# tarjeta-v8.net
KiCad netlist of a schematic drawn in EAGLE
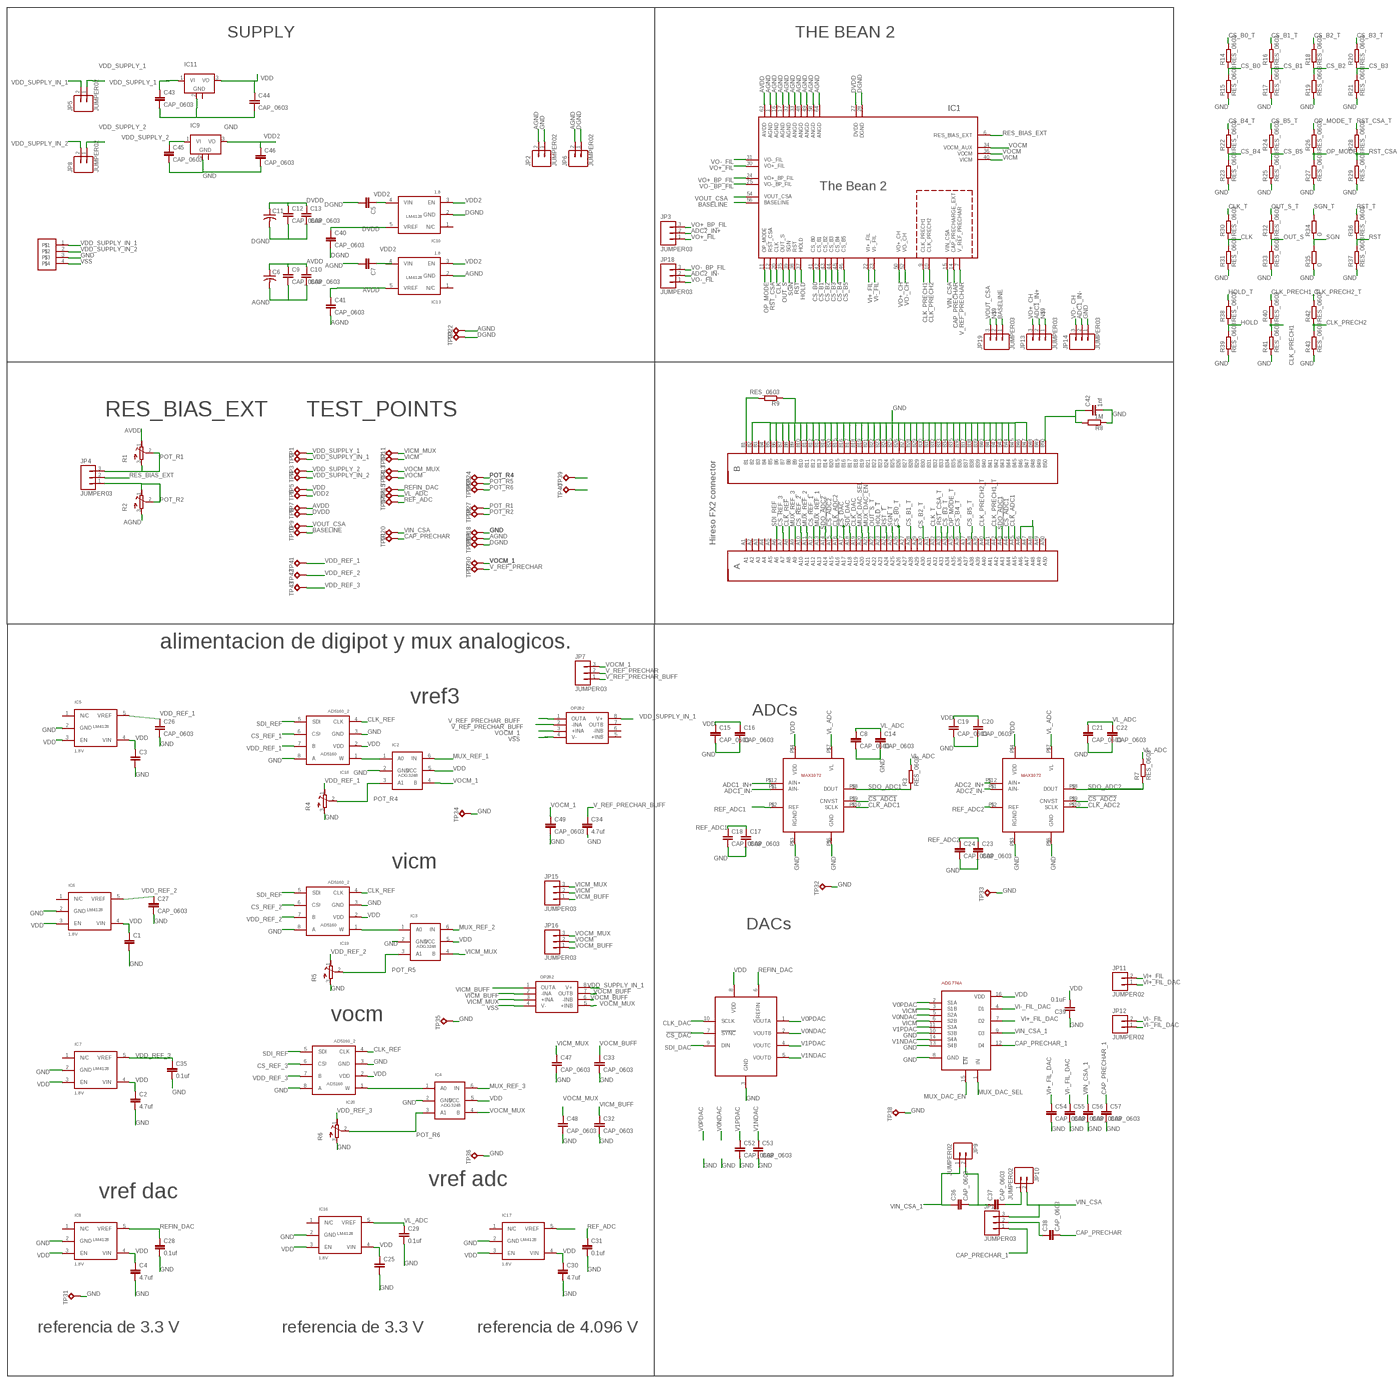
[diagram p0: schematic, sheet 1, overview]
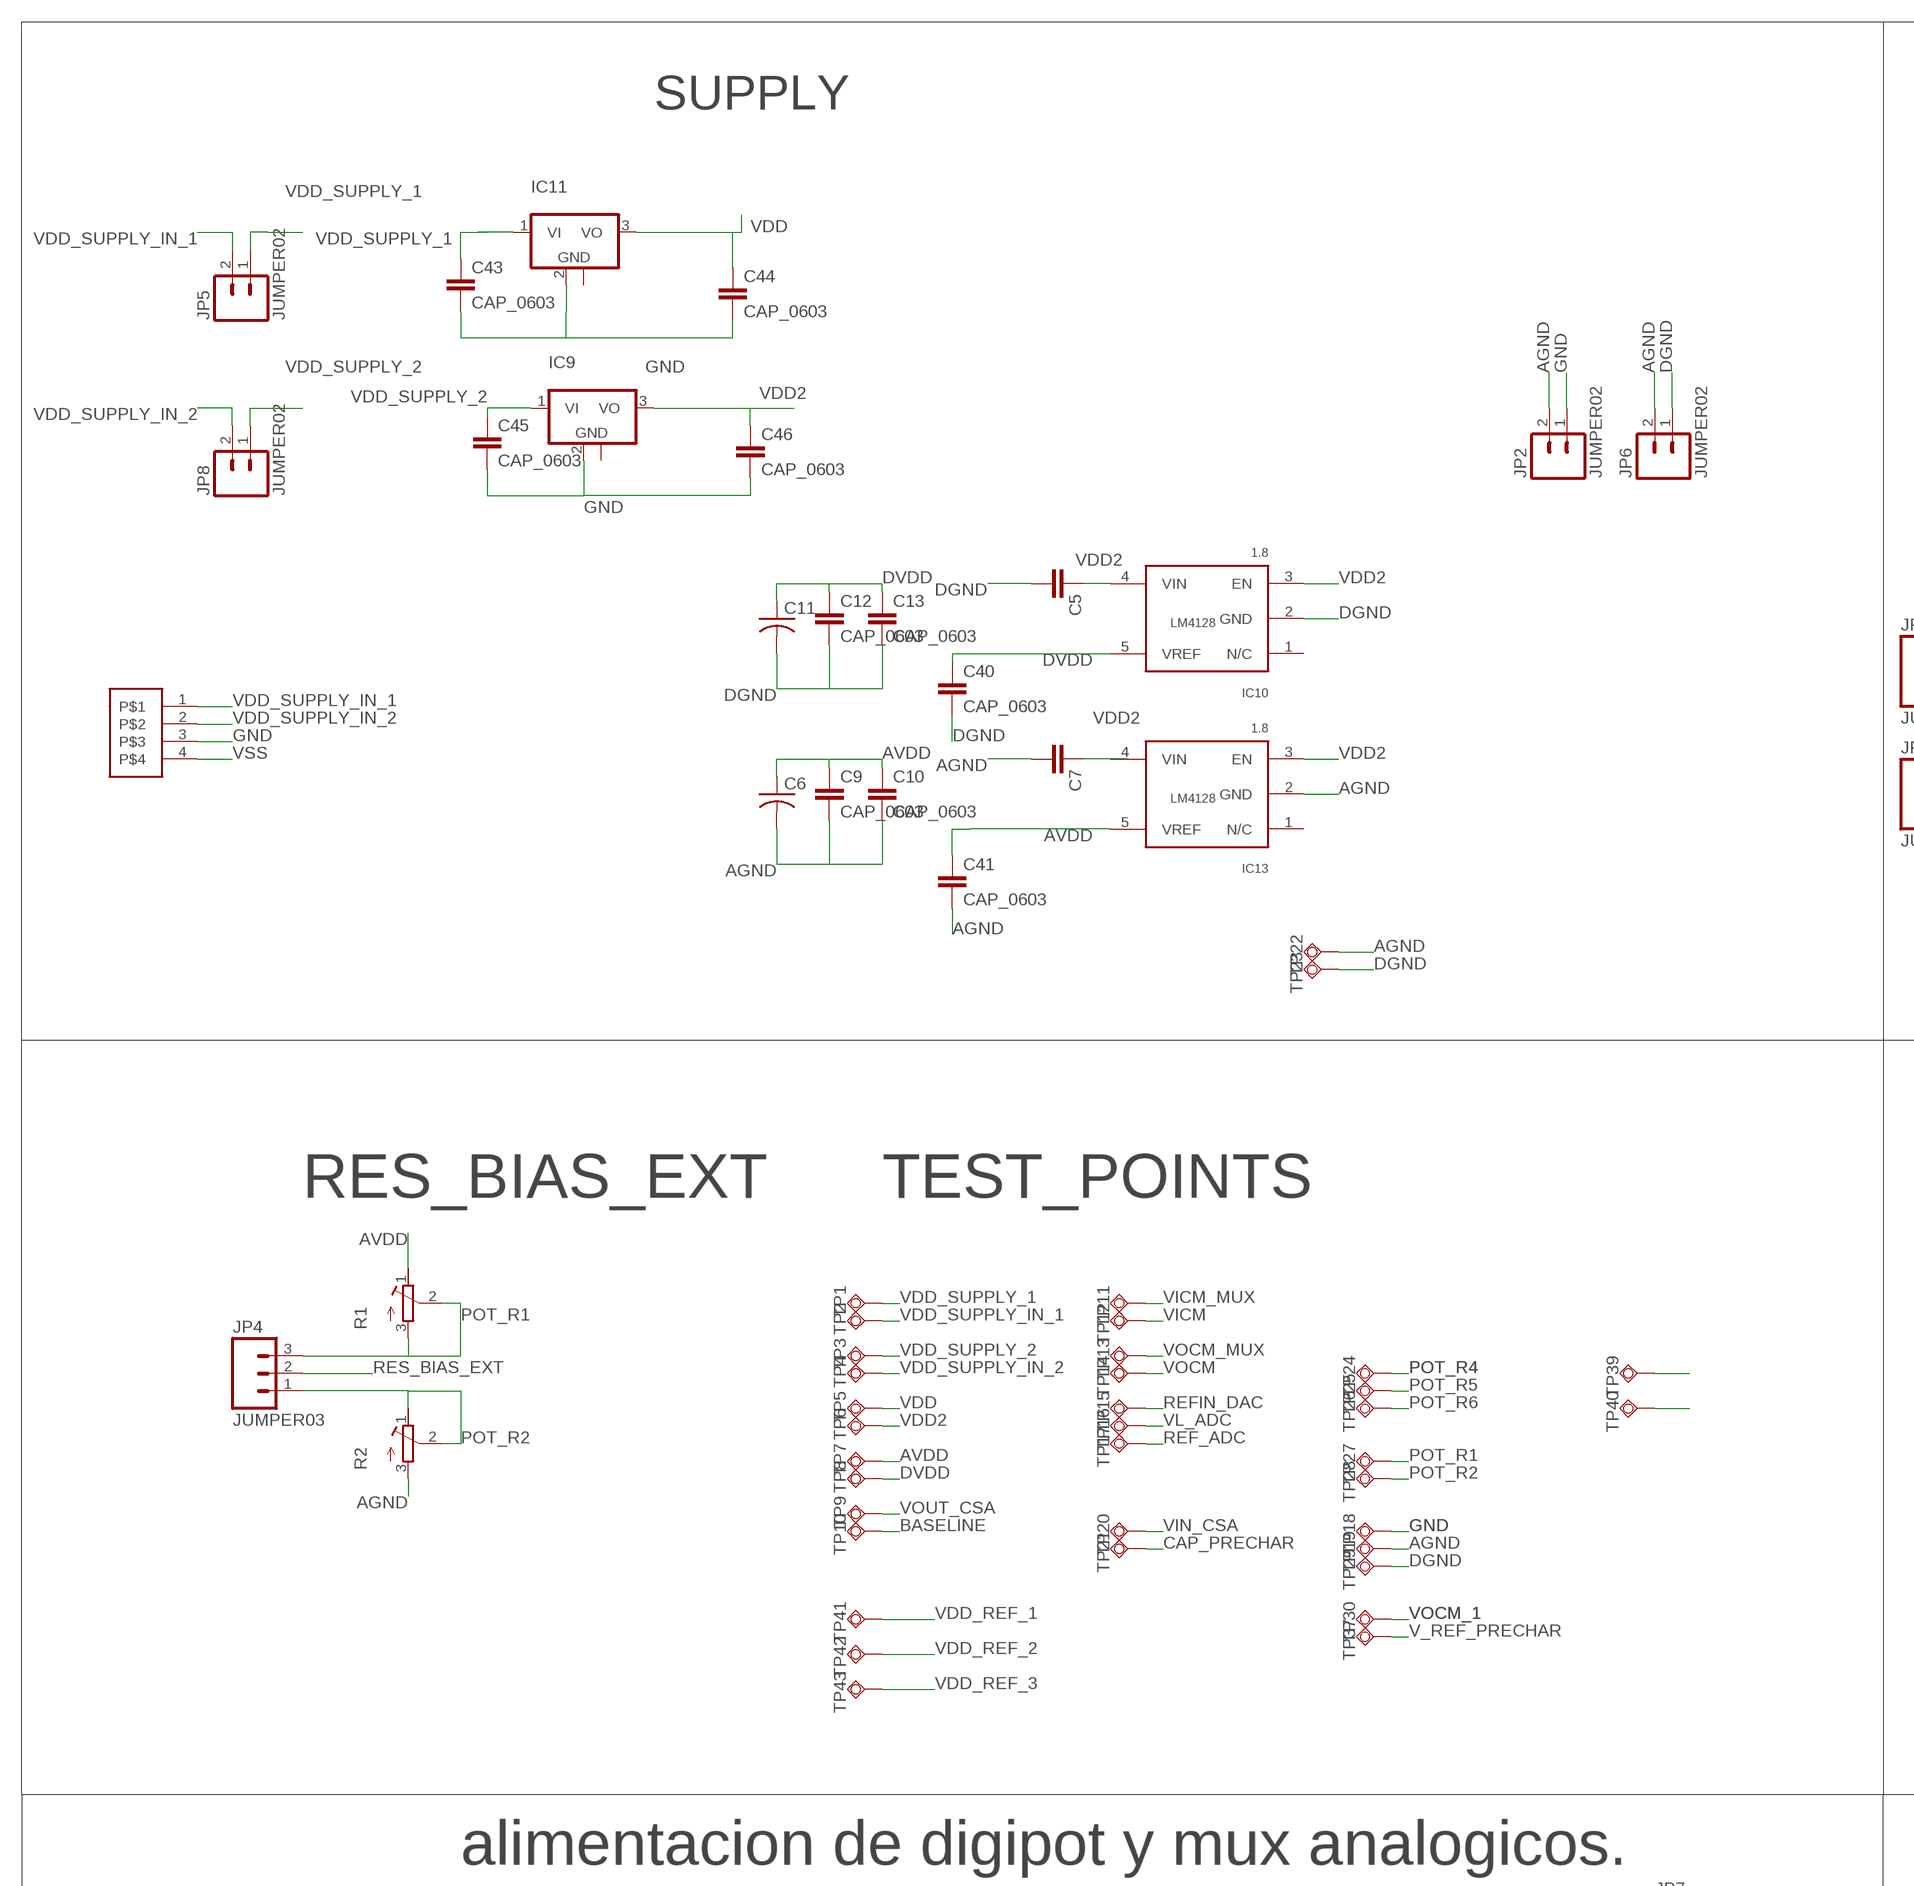
[diagram p1: schematic, sheet 1, part 1 of 4]
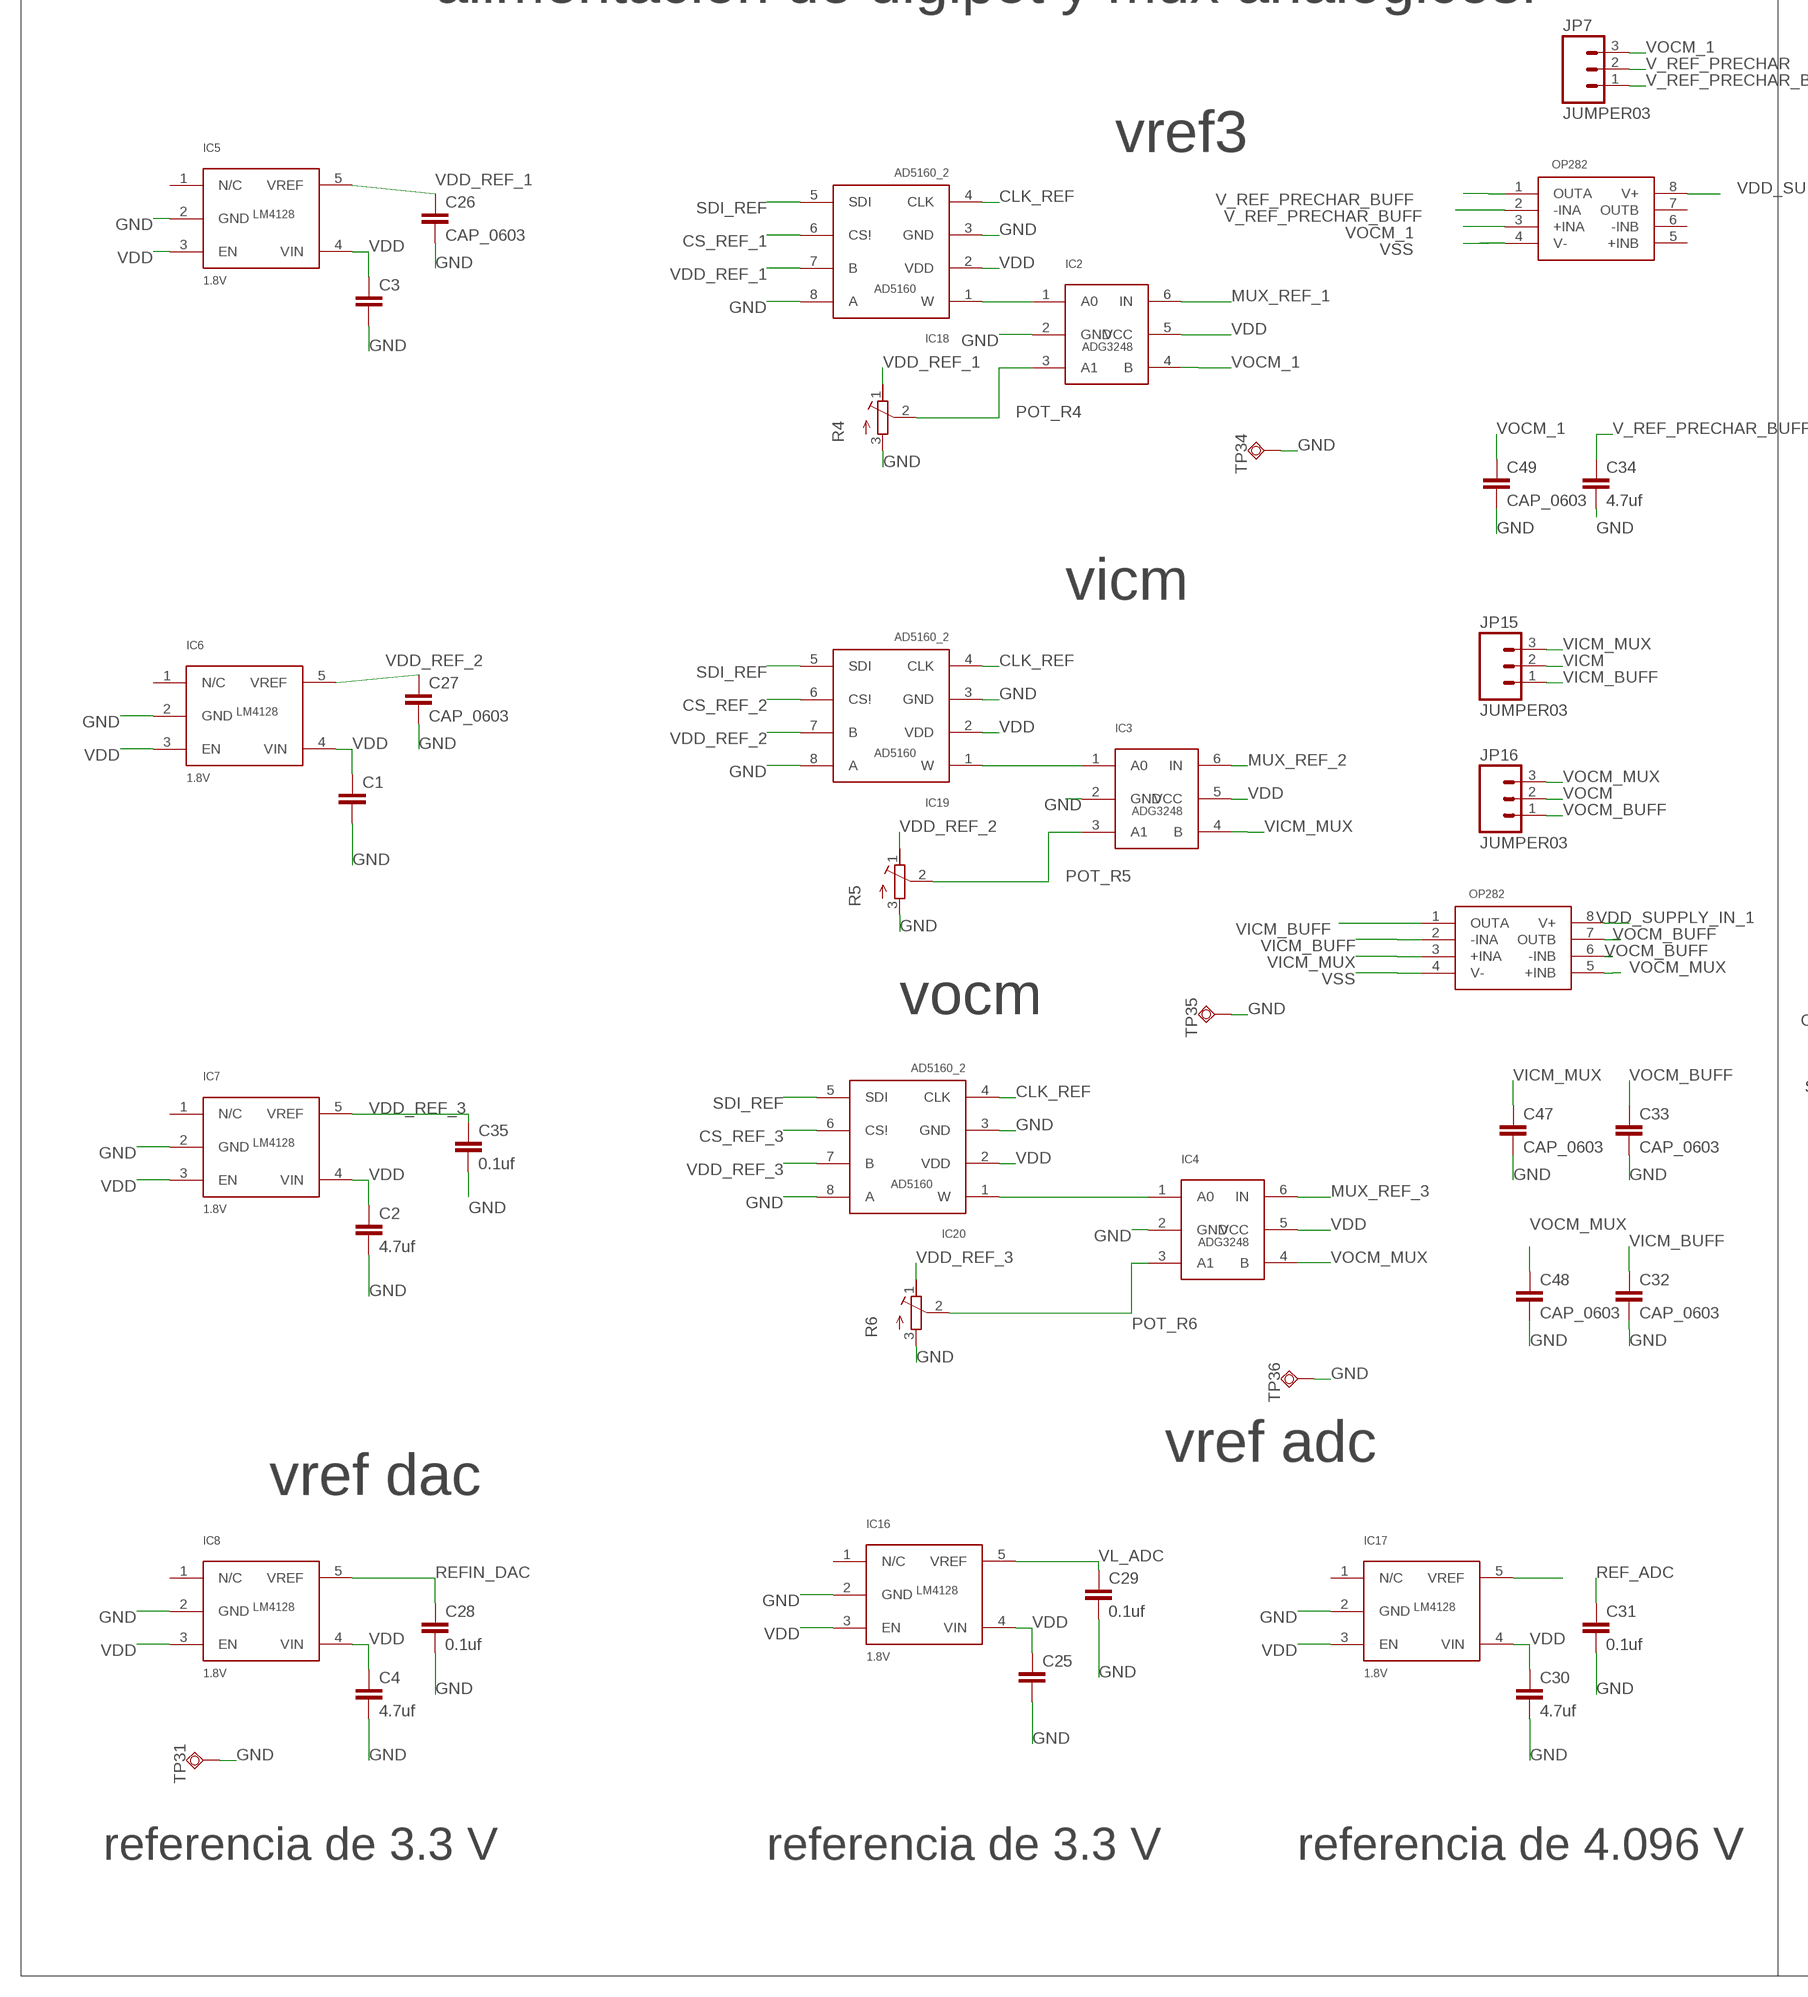
[diagram p2: schematic, sheet 1, part 2 of 4]
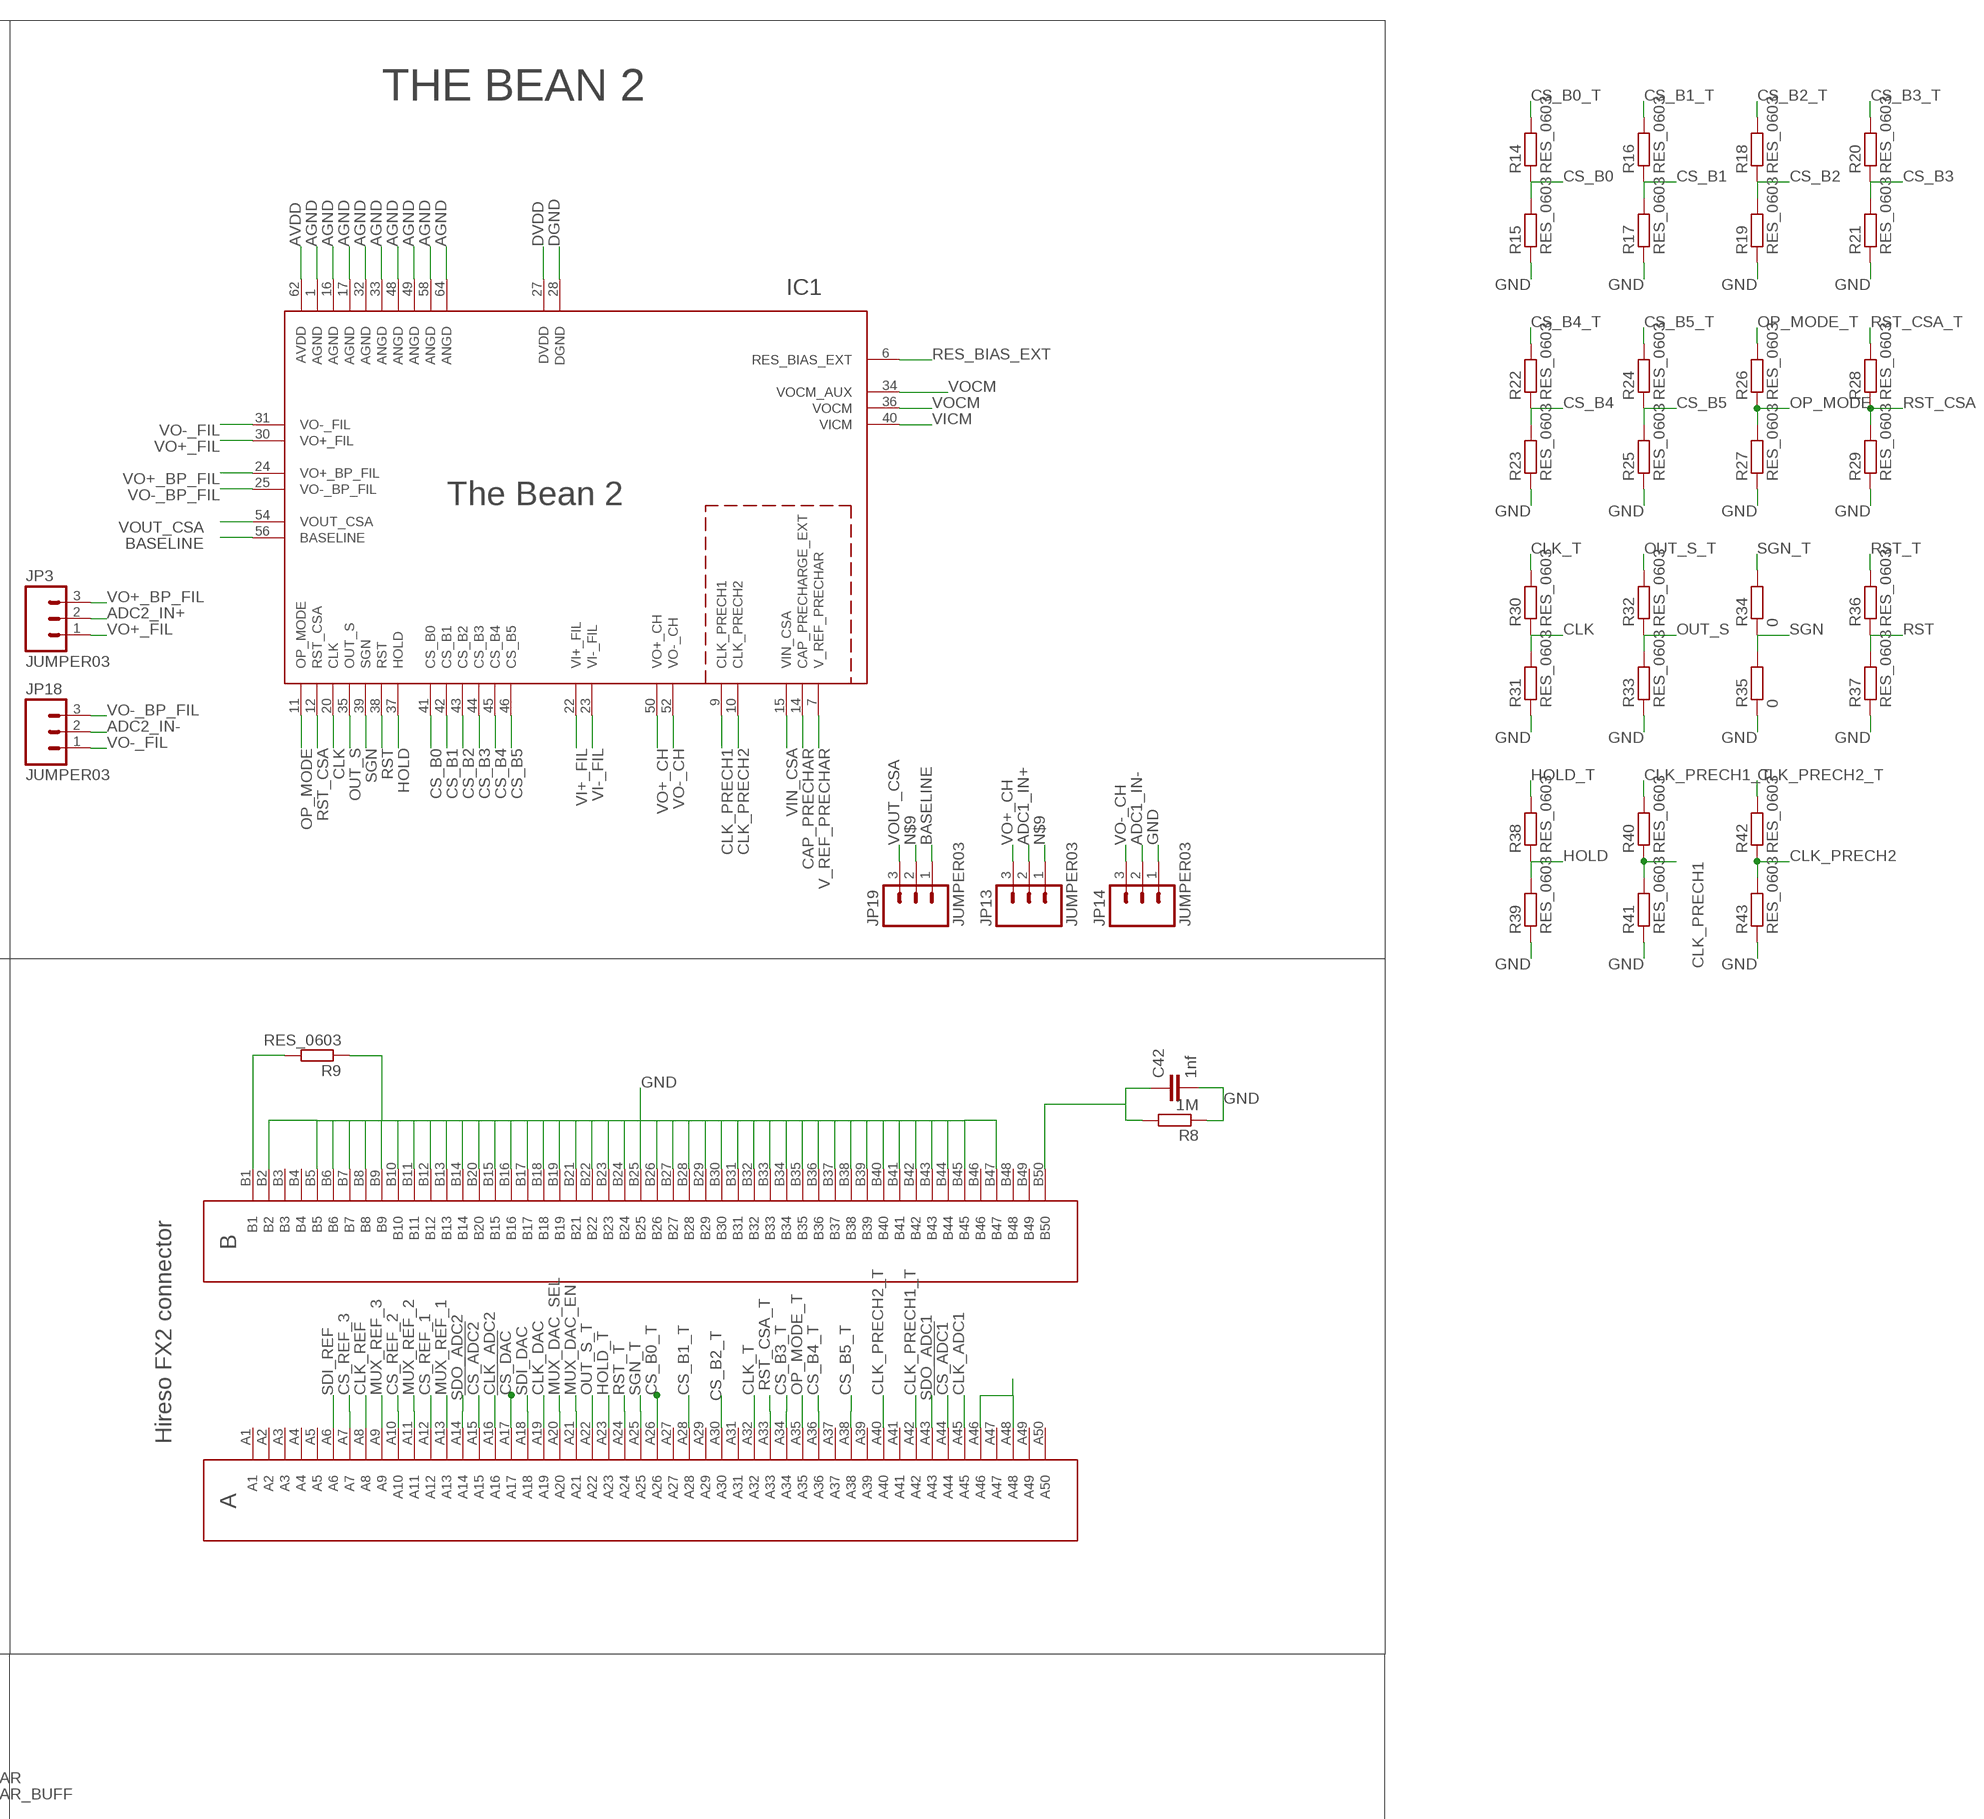
[diagram p3: schematic, sheet 1, part 3 of 4]
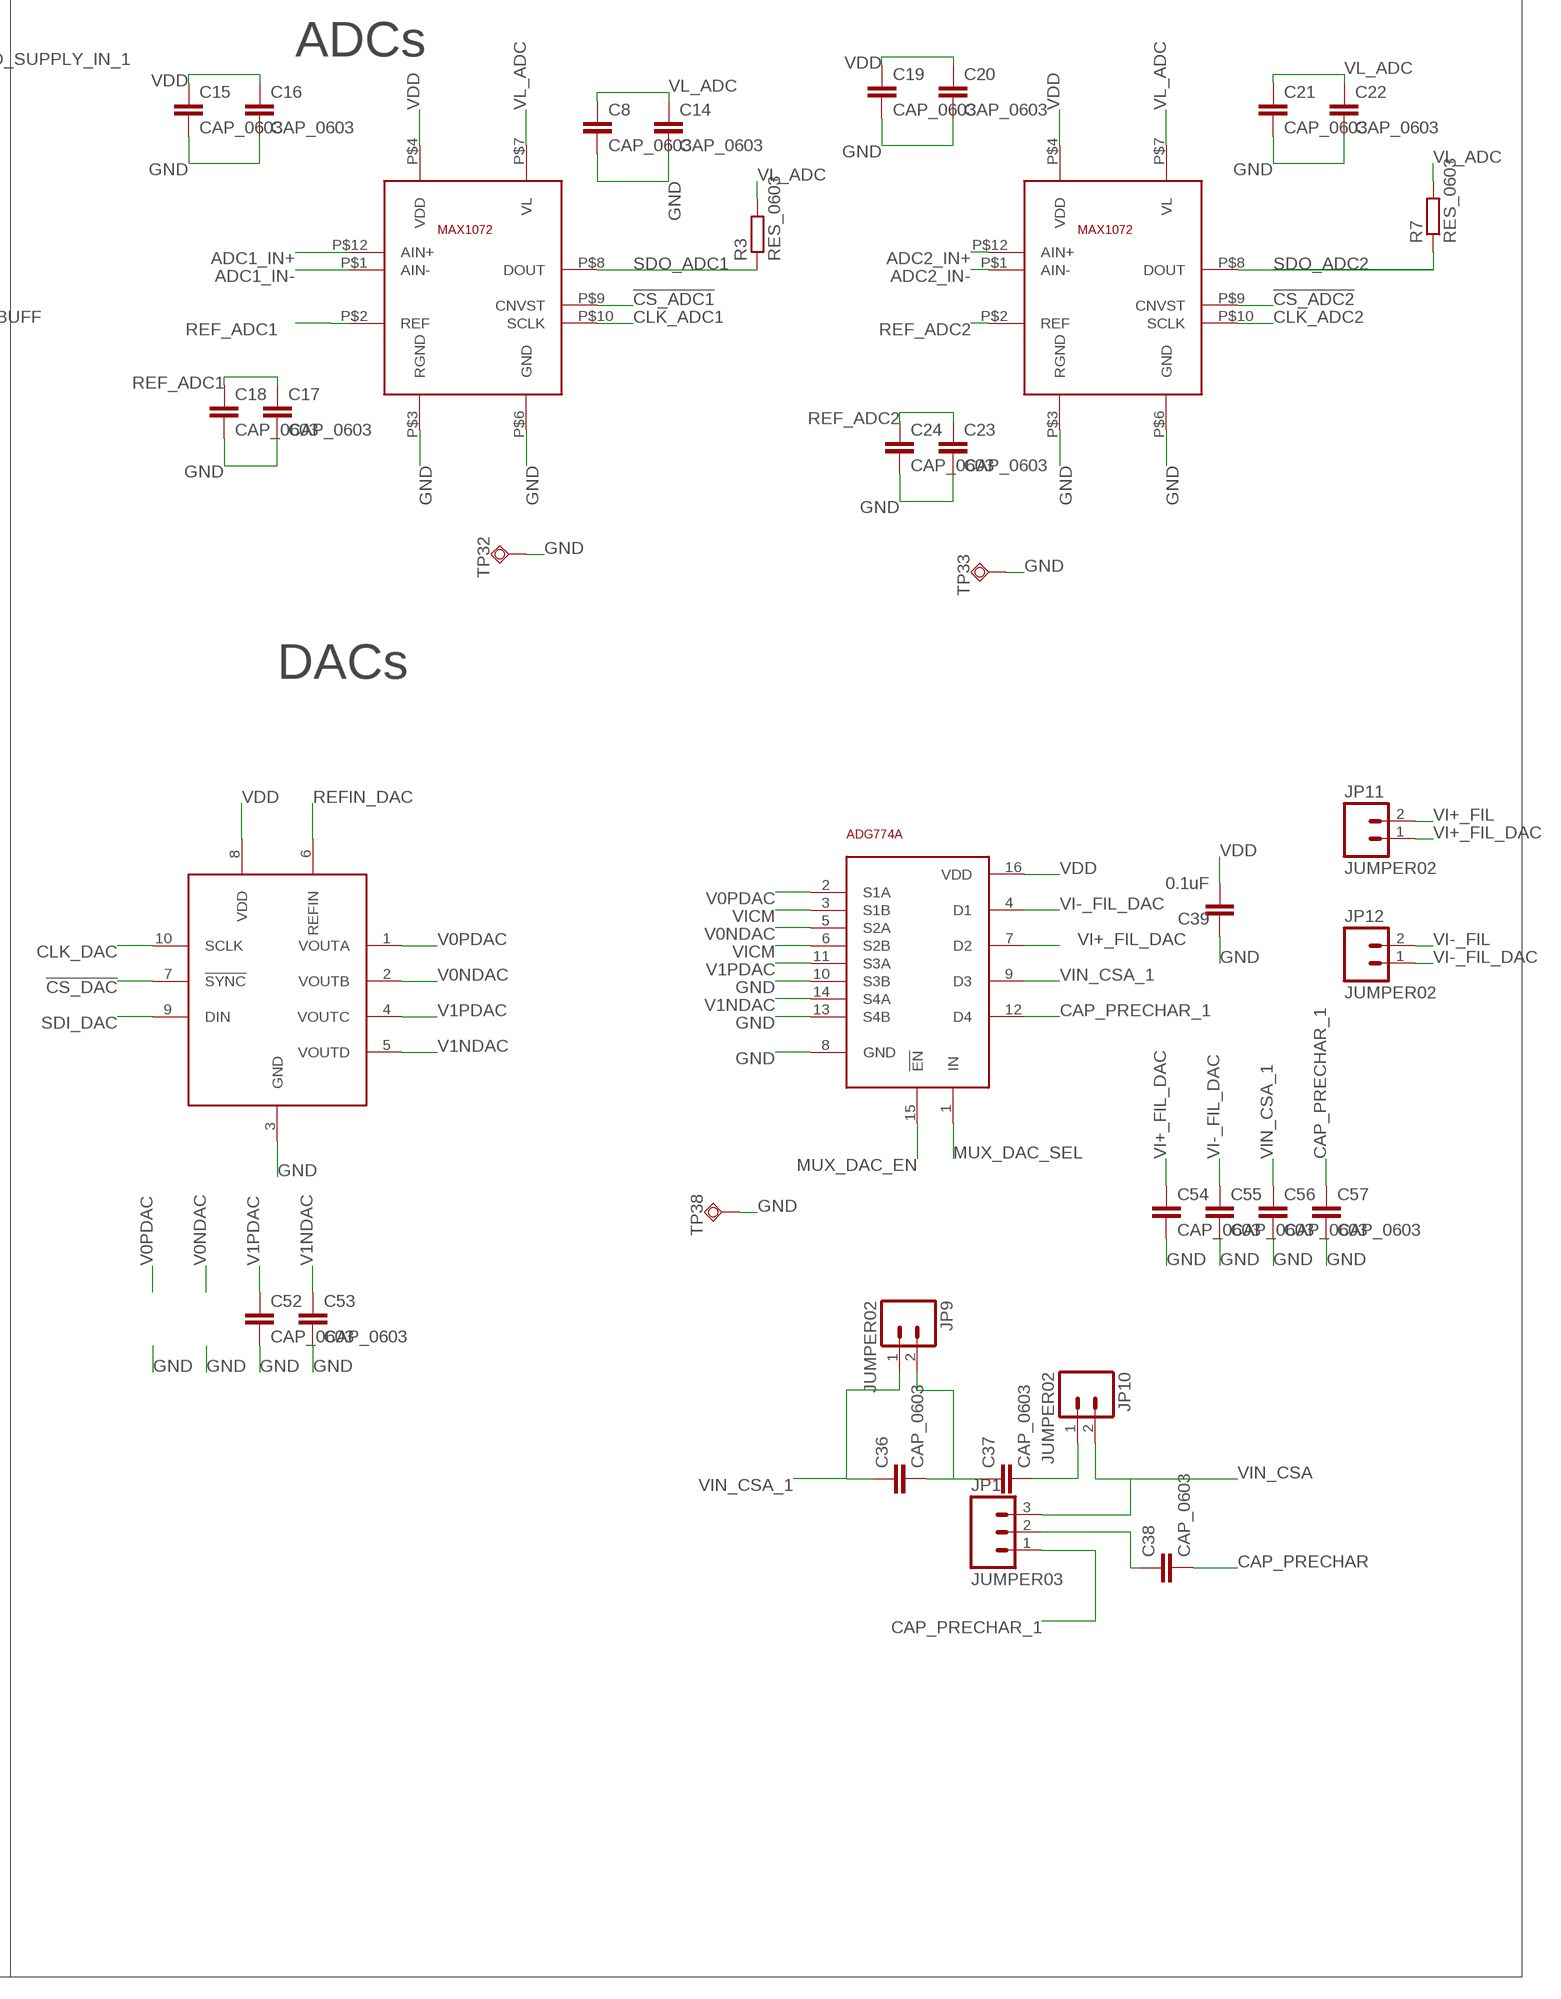
[diagram p4: schematic, sheet 1, part 4 of 4]

(export (version "E")
  (design (tool "Eeschema 10.0.6"))
  (components
    (comp (ref "C1")
      (value "CAP_0402")
      (footprint "eagle-import:C0402")
      (libsource (lib "eagle-import") (part "CAP_0402"))
    )
    (comp (ref "C2")
      (value "4.7uf")
      (footprint "eagle-import:C0402")
      (libsource (lib "eagle-import") (part "CAP_0402"))
    )
    (comp (ref "C3")
      (value "CAP_0402")
      (footprint "eagle-import:C0402")
      (libsource (lib "eagle-import") (part "CAP_0402"))
    )
    (comp (ref "C4")
      (value "4.7uf")
      (footprint "eagle-import:C0402")
      (libsource (lib "eagle-import") (part "CAP_0402"))
    )
    (comp (ref "C5")
      (value "CAP_0402")
      (footprint "eagle-import:C0402")
      (libsource (lib "eagle-import") (part "CAP_0402"))
    )
    (comp (ref "C6")
      (value "CAP_0805")
      (footprint "eagle-import:C0805")
      (libsource (lib "eagle-import") (part "CAP_0805"))
    )
    (comp (ref "C7")
      (value "CAP_0402")
      (footprint "eagle-import:C0402")
      (libsource (lib "eagle-import") (part "CAP_0402"))
    )
    (comp (ref "C8")
      (value "CAP_0603")
      (footprint "eagle-import:C0603")
      (libsource (lib "eagle-import") (part "CAP_0603"))
    )
    (comp (ref "C9")
      (value "CAP_0603")
      (footprint "eagle-import:C0603")
      (libsource (lib "eagle-import") (part "CAP_0603"))
    )
    (comp (ref "C10")
      (value "CAP_0603")
      (footprint "eagle-import:C0603")
      (libsource (lib "eagle-import") (part "CAP_0603"))
    )
    (comp (ref "C11")
      (value "CAP_0805")
      (footprint "eagle-import:C0805")
      (libsource (lib "eagle-import") (part "CAP_0805"))
    )
    (comp (ref "C12")
      (value "CAP_0603")
      (footprint "eagle-import:C0603")
      (libsource (lib "eagle-import") (part "CAP_0603"))
    )
    (comp (ref "C13")
      (value "CAP_0603")
      (footprint "eagle-import:C0603")
      (libsource (lib "eagle-import") (part "CAP_0603"))
    )
    (comp (ref "C14")
      (value "CAP_0603")
      (footprint "eagle-import:C0603")
      (libsource (lib "eagle-import") (part "CAP_0603"))
    )
    (comp (ref "C15")
      (value "CAP_0603")
      (footprint "eagle-import:C0603")
      (libsource (lib "eagle-import") (part "CAP_0603"))
    )
    (comp (ref "C16")
      (value "CAP_0603")
      (footprint "eagle-import:C0603")
      (libsource (lib "eagle-import") (part "CAP_0603"))
    )
    (comp (ref "C17")
      (value "CAP_0603")
      (footprint "eagle-import:C0603")
      (libsource (lib "eagle-import") (part "CAP_0603"))
    )
    (comp (ref "C18")
      (value "CAP_0603")
      (footprint "eagle-import:C0603")
      (libsource (lib "eagle-import") (part "CAP_0603"))
    )
    (comp (ref "C19")
      (value "CAP_0603")
      (footprint "eagle-import:C0603")
      (libsource (lib "eagle-import") (part "CAP_0603"))
    )
    (comp (ref "C20")
      (value "CAP_0603")
      (footprint "eagle-import:C0603")
      (libsource (lib "eagle-import") (part "CAP_0603"))
    )
    (comp (ref "C21")
      (value "CAP_0603")
      (footprint "eagle-import:C0603")
      (libsource (lib "eagle-import") (part "CAP_0603"))
    )
    (comp (ref "C22")
      (value "CAP_0603")
      (footprint "eagle-import:C0603")
      (libsource (lib "eagle-import") (part "CAP_0603"))
    )
    (comp (ref "C23")
      (value "CAP_0603")
      (footprint "eagle-import:C0603")
      (libsource (lib "eagle-import") (part "CAP_0603"))
    )
    (comp (ref "C24")
      (value "CAP_0603")
      (footprint "eagle-import:C0603")
      (libsource (lib "eagle-import") (part "CAP_0603"))
    )
    (comp (ref "C25")
      (value "CAP_0402")
      (footprint "eagle-import:C0402")
      (libsource (lib "eagle-import") (part "CAP_0402"))
    )
    (comp (ref "C26")
      (value "CAP_0603")
      (footprint "eagle-import:C0603")
      (libsource (lib "eagle-import") (part "CAP_0603"))
    )
    (comp (ref "C27")
      (value "CAP_0603")
      (footprint "eagle-import:C0603")
      (libsource (lib "eagle-import") (part "CAP_0603"))
    )
    (comp (ref "C28")
      (value "0.1uf")
      (footprint "eagle-import:C0603")
      (libsource (lib "eagle-import") (part "CAP_0603"))
    )
    (comp (ref "C29")
      (value "0.1uf")
      (footprint "eagle-import:C0603")
      (libsource (lib "eagle-import") (part "CAP_0603"))
    )
    (comp (ref "C30")
      (value "4.7uf")
      (footprint "eagle-import:C0402")
      (libsource (lib "eagle-import") (part "CAP_0402"))
    )
    (comp (ref "C31")
      (value "0.1uf")
      (footprint "eagle-import:C0603")
      (libsource (lib "eagle-import") (part "CAP_0603"))
    )
    (comp (ref "C32")
      (value "CAP_0603")
      (footprint "eagle-import:C0603")
      (libsource (lib "eagle-import") (part "CAP_0603"))
    )
    (comp (ref "C33")
      (value "CAP_0603")
      (footprint "eagle-import:C0603")
      (libsource (lib "eagle-import") (part "CAP_0603"))
    )
    (comp (ref "C34")
      (value "4.7uf")
      (footprint "eagle-import:C0603")
      (libsource (lib "eagle-import") (part "CAP_0603"))
    )
    (comp (ref "C35")
      (value "0.1uf")
      (footprint "eagle-import:C0603")
      (libsource (lib "eagle-import") (part "CAP_0603"))
    )
    (comp (ref "C36")
      (value "CAP_0603")
      (footprint "eagle-import:C0603")
      (libsource (lib "eagle-import") (part "CAP_0603"))
    )
    (comp (ref "C37")
      (value "CAP_0603")
      (footprint "eagle-import:C0603")
      (libsource (lib "eagle-import") (part "CAP_0603"))
    )
    (comp (ref "C38")
      (value "CAP_0603")
      (footprint "eagle-import:C0603")
      (libsource (lib "eagle-import") (part "CAP_0603"))
    )
    (comp (ref "C39")
      (value "0.1uF")
      (footprint "eagle-import:C0603")
      (libsource (lib "eagle-import") (part "CAP_0603"))
    )
    (comp (ref "C40")
      (value "CAP_0603")
      (footprint "eagle-import:C0603")
      (libsource (lib "eagle-import") (part "CAP_0603"))
    )
    (comp (ref "C41")
      (value "CAP_0603")
      (footprint "eagle-import:C0603")
      (libsource (lib "eagle-import") (part "CAP_0603"))
    )
    (comp (ref "C42")
      (value "1nf")
      (footprint "eagle-import:C0603")
      (libsource (lib "eagle-import") (part "CAP_0603"))
    )
    (comp (ref "C43")
      (value "CAP_0603")
      (footprint "eagle-import:C0603")
      (libsource (lib "eagle-import") (part "CAP_0603"))
    )
    (comp (ref "C44")
      (value "CAP_0603")
      (footprint "eagle-import:C0603")
      (libsource (lib "eagle-import") (part "CAP_0603"))
    )
    (comp (ref "C45")
      (value "CAP_0603")
      (footprint "eagle-import:C0603")
      (libsource (lib "eagle-import") (part "CAP_0603"))
    )
    (comp (ref "C46")
      (value "CAP_0603")
      (footprint "eagle-import:C0603")
      (libsource (lib "eagle-import") (part "CAP_0603"))
    )
    (comp (ref "C47")
      (value "CAP_0603")
      (footprint "eagle-import:C0603")
      (libsource (lib "eagle-import") (part "CAP_0603"))
    )
    (comp (ref "C48")
      (value "CAP_0603")
      (footprint "eagle-import:C0603")
      (libsource (lib "eagle-import") (part "CAP_0603"))
    )
    (comp (ref "C49")
      (value "CAP_0603")
      (footprint "eagle-import:C0603")
      (libsource (lib "eagle-import") (part "CAP_0603"))
    )
    (comp (ref "C52")
      (value "CAP_0603")
      (footprint "eagle-import:C0603")
      (libsource (lib "eagle-import") (part "CAP_0603"))
    )
    (comp (ref "C53")
      (value "CAP_0603")
      (footprint "eagle-import:C0603")
      (libsource (lib "eagle-import") (part "CAP_0603"))
    )
    (comp (ref "C54")
      (value "CAP_0603")
      (footprint "eagle-import:C0603")
      (libsource (lib "eagle-import") (part "CAP_0603"))
    )
    (comp (ref "C55")
      (value "CAP_0603")
      (footprint "eagle-import:C0603")
      (libsource (lib "eagle-import") (part "CAP_0603"))
    )
    (comp (ref "C56")
      (value "CAP_0603")
      (footprint "eagle-import:C0603")
      (libsource (lib "eagle-import") (part "CAP_0603"))
    )
    (comp (ref "C57")
      (value "CAP_0603")
      (footprint "eagle-import:C0603")
      (libsource (lib "eagle-import") (part "CAP_0603"))
    )
    (comp (ref "IC1")
      (value "THE_BEAN_2")
      (footprint "eagle-import:QFN64")
      (libsource (lib "eagle-import") (part "THE_BEAN_2"))
    )
    (comp (ref "IC2")
      (value "ADG3248")
      (footprint "eagle-import:SC70")
      (libsource (lib "eagle-import") (part "ADG3248"))
    )
    (comp (ref "IC3")
      (value "ADG3248")
      (footprint "eagle-import:SC70")
      (libsource (lib "eagle-import") (part "ADG3248"))
    )
    (comp (ref "IC4")
      (value "ADG3248")
      (footprint "eagle-import:SC70")
      (libsource (lib "eagle-import") (part "ADG3248"))
    )
    (comp (ref "IC5")
      (value "1.8V")
      (footprint "eagle-import:SOT23-5L_2")
      (libsource (lib "eagle-import") (part "LM4128_2"))
    )
    (comp (ref "IC6")
      (value "1.8V")
      (footprint "eagle-import:SOT23-5L_2")
      (libsource (lib "eagle-import") (part "LM4128_2"))
    )
    (comp (ref "IC7")
      (value "1.8V")
      (footprint "eagle-import:SOT23-5L_2")
      (libsource (lib "eagle-import") (part "LM4128_2"))
    )
    (comp (ref "IC8")
      (value "1.8V")
      (footprint "eagle-import:SOT23-5L_2")
      (libsource (lib "eagle-import") (part "LM4128_2"))
    )
    (comp (ref "IC9")
      (value "UA78M33DCY")
      (footprint "eagle-import:SOT223")
      (libsource (lib "eagle-import") (part "UA78MDCY33"))
    )
    (comp (ref "IC10")
      (value "1.8")
      (footprint "eagle-import:SOT23-5L_2")
      (libsource (lib "eagle-import") (part "LM4128_2"))
    )
    (comp (ref "IC11")
      (value "UA78M33DCY")
      (footprint "eagle-import:SOT223")
      (libsource (lib "eagle-import") (part "UA78MDCY33"))
    )
    (comp (ref "IC12")
      (value "OP282")
      (footprint "eagle-import:MSOP8")
      (libsource (lib "eagle-import") (part "OP282"))
    )
    (comp (ref "IC13")
      (value "1.8")
      (footprint "eagle-import:SOT23-5L_2")
      (libsource (lib "eagle-import") (part "LM4128_2"))
    )
    (comp (ref "IC14")
      (value "OP282")
      (footprint "eagle-import:MSOP8")
      (libsource (lib "eagle-import") (part "OP282"))
    )
    (comp (ref "IC16")
      (value "1.8V")
      (footprint "eagle-import:SOT23-5L_2")
      (libsource (lib "eagle-import") (part "LM4128_2"))
    )
    (comp (ref "IC17")
      (value "1.8V")
      (footprint "eagle-import:SOT23-5L_2")
      (libsource (lib "eagle-import") (part "LM4128_2"))
    )
    (comp (ref "IC18")
      (value "AD5160_2")
      (footprint "eagle-import:SOT23-8_2")
      (libsource (lib "eagle-import") (part "AD5160_2"))
    )
    (comp (ref "IC19")
      (value "AD5160_2")
      (footprint "eagle-import:SOT23-8_2")
      (libsource (lib "eagle-import") (part "AD5160_2"))
    )
    (comp (ref "IC20")
      (value "AD5160_2")
      (footprint "eagle-import:SOT23-8_2")
      (libsource (lib "eagle-import") (part "AD5160_2"))
    )
    (comp (ref "IC21")
      (value "ADG774A")
      (footprint "eagle-import:QSOP16")
      (libsource (lib "eagle-import") (part "ADG774A"))
    )
    (comp (ref "IC22")
      (value "MAX1072")
      (footprint "eagle-import:TQFN12")
      (libsource (lib "eagle-import") (part "MAX1072"))
    )
    (comp (ref "IC23")
      (value "DAC7554")
      (footprint "eagle-import:MSOP10")
      (libsource (lib "eagle-import") (part "DAC7554"))
    )
    (comp (ref "J1")
      (value "HIRESO_FX_CONNECTOR")
      (footprint "eagle-import:FX2-100S-1.27")
      (libsource (lib "eagle-import") (part "HIRESO_FX_CONNECTOR"))
    )
    (comp (ref "JP1")
      (value "JUMPER03")
      (footprint "eagle-import:1X03")
      (libsource (lib "eagle-import") (part "JUMPER03"))
    )
    (comp (ref "JP2")
      (value "JUMPER02")
      (footprint "eagle-import:1X02")
      (libsource (lib "eagle-import") (part "JUMPER02"))
    )
    (comp (ref "JP3")
      (value "JUMPER03")
      (footprint "eagle-import:1X03")
      (libsource (lib "eagle-import") (part "JUMPER03"))
    )
    (comp (ref "JP4")
      (value "JUMPER03")
      (footprint "eagle-import:1X03")
      (libsource (lib "eagle-import") (part "JUMPER03"))
    )
    (comp (ref "JP5")
      (value "JUMPER02")
      (footprint "eagle-import:1X02")
      (libsource (lib "eagle-import") (part "JUMPER02"))
    )
    (comp (ref "JP6")
      (value "JUMPER02")
      (footprint "eagle-import:1X02")
      (libsource (lib "eagle-import") (part "JUMPER02"))
    )
    (comp (ref "JP7")
      (value "JUMPER03")
      (footprint "eagle-import:1X03")
      (libsource (lib "eagle-import") (part "JUMPER03"))
    )
    (comp (ref "JP8")
      (value "JUMPER02")
      (footprint "eagle-import:1X02")
      (libsource (lib "eagle-import") (part "JUMPER02"))
    )
    (comp (ref "JP9")
      (value "JUMPER02")
      (footprint "eagle-import:1X02")
      (libsource (lib "eagle-import") (part "JUMPER02"))
    )
    (comp (ref "JP10")
      (value "JUMPER02")
      (footprint "eagle-import:1X02")
      (libsource (lib "eagle-import") (part "JUMPER02"))
    )
    (comp (ref "JP11")
      (value "JUMPER02")
      (footprint "eagle-import:1X02")
      (libsource (lib "eagle-import") (part "JUMPER02"))
    )
    (comp (ref "JP12")
      (value "JUMPER02")
      (footprint "eagle-import:1X02")
      (libsource (lib "eagle-import") (part "JUMPER02"))
    )
    (comp (ref "JP13")
      (value "JUMPER03")
      (footprint "eagle-import:1X03")
      (libsource (lib "eagle-import") (part "JUMPER03"))
    )
    (comp (ref "JP14")
      (value "JUMPER03")
      (footprint "eagle-import:1X03")
      (libsource (lib "eagle-import") (part "JUMPER03"))
    )
    (comp (ref "JP15")
      (value "JUMPER03")
      (footprint "eagle-import:1X03")
      (libsource (lib "eagle-import") (part "JUMPER03"))
    )
    (comp (ref "JP16")
      (value "JUMPER03")
      (footprint "eagle-import:1X03")
      (libsource (lib "eagle-import") (part "JUMPER03"))
    )
    (comp (ref "JP17")
      (value "JUMPER04")
      (footprint "eagle-import:1X04")
      (libsource (lib "eagle-import") (part "JUMPER04"))
    )
    (comp (ref "JP18")
      (value "JUMPER03")
      (footprint "eagle-import:1X03")
      (libsource (lib "eagle-import") (part "JUMPER03"))
    )
    (comp (ref "JP19")
      (value "JUMPER03")
      (footprint "eagle-import:1X03")
      (libsource (lib "eagle-import") (part "JUMPER03"))
    )
    (comp (ref "R1")
      (value "TRIMMER_ST5")
      (footprint "eagle-import:ST-5EW")
      (libsource (lib "eagle-import") (part "TRIMMER_ST5"))
    )
    (comp (ref "R2")
      (value "TRIMMER_ST5")
      (footprint "eagle-import:ST-5EW")
      (libsource (lib "eagle-import") (part "TRIMMER_ST5"))
    )
    (comp (ref "R3")
      (value "RES_0603")
      (footprint "eagle-import:R0603")
      (libsource (lib "eagle-import") (part "RES_0603"))
    )
    (comp (ref "R4")
      (value "TRIMMER_ST5")
      (footprint "eagle-import:ST-5EW")
      (libsource (lib "eagle-import") (part "TRIMMER_ST5"))
    )
    (comp (ref "R5")
      (value "TRIMMER_ST5")
      (footprint "eagle-import:ST-5EW")
      (libsource (lib "eagle-import") (part "TRIMMER_ST5"))
    )
    (comp (ref "R6")
      (value "TRIMMER_ST5")
      (footprint "eagle-import:ST-5EW")
      (libsource (lib "eagle-import") (part "TRIMMER_ST5"))
    )
    (comp (ref "R7")
      (value "RES_0603")
      (footprint "eagle-import:R0603")
      (libsource (lib "eagle-import") (part "RES_0603"))
    )
    (comp (ref "R8")
      (value "1M")
      (footprint "eagle-import:R0603")
      (libsource (lib "eagle-import") (part "RES_0603"))
    )
    (comp (ref "R9")
      (value "RES_0603")
      (footprint "eagle-import:R0603")
      (libsource (lib "eagle-import") (part "RES_0603"))
    )
    (comp (ref "R14")
      (value "RES_0603")
      (footprint "eagle-import:R0603")
      (libsource (lib "eagle-import") (part "RES_0603"))
    )
    (comp (ref "R15")
      (value "RES_0603")
      (footprint "eagle-import:R0603")
      (libsource (lib "eagle-import") (part "RES_0603"))
    )
    (comp (ref "R16")
      (value "RES_0603")
      (footprint "eagle-import:R0603")
      (libsource (lib "eagle-import") (part "RES_0603"))
    )
    (comp (ref "R17")
      (value "RES_0603")
      (footprint "eagle-import:R0603")
      (libsource (lib "eagle-import") (part "RES_0603"))
    )
    (comp (ref "R18")
      (value "RES_0603")
      (footprint "eagle-import:R0603")
      (libsource (lib "eagle-import") (part "RES_0603"))
    )
    (comp (ref "R19")
      (value "RES_0603")
      (footprint "eagle-import:R0603")
      (libsource (lib "eagle-import") (part "RES_0603"))
    )
    (comp (ref "R20")
      (value "RES_0603")
      (footprint "eagle-import:R0603")
      (libsource (lib "eagle-import") (part "RES_0603"))
    )
    (comp (ref "R21")
      (value "RES_0603")
      (footprint "eagle-import:R0603")
      (libsource (lib "eagle-import") (part "RES_0603"))
    )
    (comp (ref "R22")
      (value "RES_0603")
      (footprint "eagle-import:R0603")
      (libsource (lib "eagle-import") (part "RES_0603"))
    )
    (comp (ref "R23")
      (value "RES_0603")
      (footprint "eagle-import:R0603")
      (libsource (lib "eagle-import") (part "RES_0603"))
    )
    (comp (ref "R24")
      (value "RES_0603")
      (footprint "eagle-import:R0603")
      (libsource (lib "eagle-import") (part "RES_0603"))
    )
    (comp (ref "R25")
      (value "RES_0603")
      (footprint "eagle-import:R0603")
      (libsource (lib "eagle-import") (part "RES_0603"))
    )
    (comp (ref "R26")
      (value "RES_0603")
      (footprint "eagle-import:R0603")
      (libsource (lib "eagle-import") (part "RES_0603"))
    )
    (comp (ref "R27")
      (value "RES_0603")
      (footprint "eagle-import:R0603")
      (libsource (lib "eagle-import") (part "RES_0603"))
    )
    (comp (ref "R28")
      (value "RES_0603")
      (footprint "eagle-import:R0603")
      (libsource (lib "eagle-import") (part "RES_0603"))
    )
    (comp (ref "R29")
      (value "RES_0603")
      (footprint "eagle-import:R0603")
      (libsource (lib "eagle-import") (part "RES_0603"))
    )
    (comp (ref "R30")
      (value "RES_0603")
      (footprint "eagle-import:R0603")
      (libsource (lib "eagle-import") (part "RES_0603"))
    )
    (comp (ref "R31")
      (value "RES_0603")
      (footprint "eagle-import:R0603")
      (libsource (lib "eagle-import") (part "RES_0603"))
    )
    (comp (ref "R32")
      (value "RES_0603")
      (footprint "eagle-import:R0603")
      (libsource (lib "eagle-import") (part "RES_0603"))
    )
    (comp (ref "R33")
      (value "RES_0603")
      (footprint "eagle-import:R0603")
      (libsource (lib "eagle-import") (part "RES_0603"))
    )
    (comp (ref "R34")
      (value "0")
      (footprint "eagle-import:R0603")
      (libsource (lib "eagle-import") (part "RES_0603"))
    )
    (comp (ref "R35")
      (value "0")
      (footprint "eagle-import:R0603")
      (libsource (lib "eagle-import") (part "RES_0603"))
    )
    (comp (ref "R36")
      (value "RES_0603")
      (footprint "eagle-import:R0603")
      (libsource (lib "eagle-import") (part "RES_0603"))
    )
    (comp (ref "R37")
      (value "RES_0603")
      (footprint "eagle-import:R0603")
      (libsource (lib "eagle-import") (part "RES_0603"))
    )
    (comp (ref "R38")
      (value "RES_0603")
      (footprint "eagle-import:R0603")
      (libsource (lib "eagle-import") (part "RES_0603"))
    )
    (comp (ref "R39")
      (value "RES_0603")
      (footprint "eagle-import:R0603")
      (libsource (lib "eagle-import") (part "RES_0603"))
    )
    (comp (ref "R40")
      (value "RES_0603")
      (footprint "eagle-import:R0603")
      (libsource (lib "eagle-import") (part "RES_0603"))
    )
    (comp (ref "R41")
      (value "RES_0603")
      (footprint "eagle-import:R0603")
      (libsource (lib "eagle-import") (part "RES_0603"))
    )
    (comp (ref "R42")
      (value "RES_0603")
      (footprint "eagle-import:R0603")
      (libsource (lib "eagle-import") (part "RES_0603"))
    )
    (comp (ref "R43")
      (value "RES_0603")
      (footprint "eagle-import:R0603")
      (libsource (lib "eagle-import") (part "RES_0603"))
    )
    (comp (ref "TP1")
      (value "TEST_POINT")
      (footprint "eagle-import:TP")
      (libsource (lib "eagle-import") (part "TEST_POINT"))
    )
    (comp (ref "TP2")
      (value "TEST_POINT")
      (footprint "eagle-import:TP")
      (libsource (lib "eagle-import") (part "TEST_POINT"))
    )
    (comp (ref "TP3")
      (value "TEST_POINT")
      (footprint "eagle-import:TP")
      (libsource (lib "eagle-import") (part "TEST_POINT"))
    )
    (comp (ref "TP4")
      (value "TEST_POINT")
      (footprint "eagle-import:TP")
      (libsource (lib "eagle-import") (part "TEST_POINT"))
    )
    (comp (ref "TP5")
      (value "TEST_POINT")
      (footprint "eagle-import:TP")
      (libsource (lib "eagle-import") (part "TEST_POINT"))
    )
    (comp (ref "TP6")
      (value "TEST_POINT")
      (footprint "eagle-import:TP")
      (libsource (lib "eagle-import") (part "TEST_POINT"))
    )
    (comp (ref "TP7")
      (value "TEST_POINT")
      (footprint "eagle-import:TP")
      (libsource (lib "eagle-import") (part "TEST_POINT"))
    )
    (comp (ref "TP8")
      (value "TEST_POINT")
      (footprint "eagle-import:TP")
      (libsource (lib "eagle-import") (part "TEST_POINT"))
    )
    (comp (ref "TP9")
      (value "TEST_POINT")
      (footprint "eagle-import:TP")
      (libsource (lib "eagle-import") (part "TEST_POINT"))
    )
    (comp (ref "TP10")
      (value "TEST_POINT")
      (footprint "eagle-import:TP")
      (libsource (lib "eagle-import") (part "TEST_POINT"))
    )
    (comp (ref "TP11")
      (value "TEST_POINT")
      (footprint "eagle-import:TP")
      (libsource (lib "eagle-import") (part "TEST_POINT"))
    )
    (comp (ref "TP12")
      (value "TEST_POINT")
      (footprint "eagle-import:TP")
      (libsource (lib "eagle-import") (part "TEST_POINT"))
    )
    (comp (ref "TP13")
      (value "TEST_POINT")
      (footprint "eagle-import:TP")
      (libsource (lib "eagle-import") (part "TEST_POINT"))
    )
    (comp (ref "TP14")
      (value "TEST_POINT")
      (footprint "eagle-import:TP")
      (libsource (lib "eagle-import") (part "TEST_POINT"))
    )
    (comp (ref "TP15")
      (value "TEST_POINT")
      (footprint "eagle-import:TP")
      (libsource (lib "eagle-import") (part "TEST_POINT"))
    )
    (comp (ref "TP16")
      (value "TEST_POINT")
      (footprint "eagle-import:TP")
      (libsource (lib "eagle-import") (part "TEST_POINT"))
    )
    (comp (ref "TP17")
      (value "TEST_POINT")
      (footprint "eagle-import:TP")
      (libsource (lib "eagle-import") (part "TEST_POINT"))
    )
    (comp (ref "TP18")
      (value "TEST_POINT")
      (footprint "eagle-import:TP")
      (libsource (lib "eagle-import") (part "TEST_POINT"))
    )
    (comp (ref "TP19")
      (value "TEST_POINT")
      (footprint "eagle-import:TP")
      (libsource (lib "eagle-import") (part "TEST_POINT"))
    )
    (comp (ref "TP20")
      (value "TEST_POINT")
      (footprint "eagle-import:TP")
      (libsource (lib "eagle-import") (part "TEST_POINT"))
    )
    (comp (ref "TP21")
      (value "TEST_POINT")
      (footprint "eagle-import:TP")
      (libsource (lib "eagle-import") (part "TEST_POINT"))
    )
    (comp (ref "TP22")
      (value "TEST_POINT")
      (footprint "eagle-import:TP")
      (libsource (lib "eagle-import") (part "TEST_POINT"))
    )
    (comp (ref "TP23")
      (value "TEST_POINT")
      (footprint "eagle-import:TP")
      (libsource (lib "eagle-import") (part "TEST_POINT"))
    )
    (comp (ref "TP24")
      (value "TEST_POINT")
      (footprint "eagle-import:TP")
      (libsource (lib "eagle-import") (part "TEST_POINT"))
    )
    (comp (ref "TP25")
      (value "TEST_POINT")
      (footprint "eagle-import:TP")
      (libsource (lib "eagle-import") (part "TEST_POINT"))
    )
    (comp (ref "TP26")
      (value "TEST_POINT")
      (footprint "eagle-import:TP")
      (libsource (lib "eagle-import") (part "TEST_POINT"))
    )
    (comp (ref "TP27")
      (value "TEST_POINT")
      (footprint "eagle-import:TP")
      (libsource (lib "eagle-import") (part "TEST_POINT"))
    )
    (comp (ref "TP28")
      (value "TEST_POINT")
      (footprint "eagle-import:TP")
      (libsource (lib "eagle-import") (part "TEST_POINT"))
    )
    (comp (ref "TP29")
      (value "TEST_POINT")
      (footprint "eagle-import:TP")
      (libsource (lib "eagle-import") (part "TEST_POINT"))
    )
    (comp (ref "TP30")
      (value "TEST_POINT")
      (footprint "eagle-import:TP")
      (libsource (lib "eagle-import") (part "TEST_POINT"))
    )
    (comp (ref "TP31")
      (value "TEST_POINT")
      (footprint "eagle-import:TP")
      (libsource (lib "eagle-import") (part "TEST_POINT"))
    )
    (comp (ref "TP32")
      (value "TEST_POINT")
      (footprint "eagle-import:TP")
      (libsource (lib "eagle-import") (part "TEST_POINT"))
    )
    (comp (ref "TP33")
      (value "TEST_POINT")
      (footprint "eagle-import:TP")
      (libsource (lib "eagle-import") (part "TEST_POINT"))
    )
    (comp (ref "TP34")
      (value "TEST_POINT")
      (footprint "eagle-import:TP")
      (libsource (lib "eagle-import") (part "TEST_POINT"))
    )
    (comp (ref "TP35")
      (value "TEST_POINT")
      (footprint "eagle-import:TP")
      (libsource (lib "eagle-import") (part "TEST_POINT"))
    )
    (comp (ref "TP36")
      (value "TEST_POINT")
      (footprint "eagle-import:TP")
      (libsource (lib "eagle-import") (part "TEST_POINT"))
    )
    (comp (ref "TP37")
      (value "TEST_POINT")
      (footprint "eagle-import:TP")
      (libsource (lib "eagle-import") (part "TEST_POINT"))
    )
    (comp (ref "TP38")
      (value "TEST_POINT")
      (footprint "eagle-import:TP")
      (libsource (lib "eagle-import") (part "TEST_POINT"))
    )
    (comp (ref "TP39")
      (value "TEST_POINT")
      (footprint "eagle-import:TP")
      (libsource (lib "eagle-import") (part "TEST_POINT"))
    )
    (comp (ref "TP40")
      (value "TEST_POINT")
      (footprint "eagle-import:TP")
      (libsource (lib "eagle-import") (part "TEST_POINT"))
    )
    (comp (ref "TP41")
      (value "TEST_POINT")
      (footprint "eagle-import:TP")
      (libsource (lib "eagle-import") (part "TEST_POINT"))
    )
    (comp (ref "TP42")
      (value "TEST_POINT")
      (footprint "eagle-import:TP")
      (libsource (lib "eagle-import") (part "TEST_POINT"))
    )
    (comp (ref "TP43")
      (value "TEST_POINT")
      (footprint "eagle-import:TP")
      (libsource (lib "eagle-import") (part "TEST_POINT"))
    )
    (comp (ref "U$5")
      (value "MAX1072")
      (footprint "eagle-import:TQFN12")
      (libsource (lib "eagle-import") (part "MAX1072"))
    )
  )
  (nets
    (net (code "1") (name "/ADC1_IN+") (class "Default")
      (node (ref "IC22") (pin "P$12") (pinfunction "AIN+_P$12") (pintype "bidirectional"))
      (node (ref "JP13") (pin "2") (pinfunction "2_2") (pintype "passive"))
    )
    (net (code "2") (name "/ADC1_IN-") (class "Default")
      (node (ref "IC22") (pin "P$1") (pinfunction "AIN-_P$1") (pintype "bidirectional"))
      (node (ref "JP14") (pin "2") (pinfunction "2_2") (pintype "passive"))
    )
    (net (code "3") (name "/ADC2_IN+") (class "Default")
      (node (ref "JP3") (pin "2") (pinfunction "2_2") (pintype "passive"))
      (node (ref "U$5") (pin "P$12") (pinfunction "AIN+_P$12") (pintype "bidirectional"))
    )
    (net (code "4") (name "/ADC2_IN-") (class "Default")
      (node (ref "JP18") (pin "2") (pinfunction "2_2") (pintype "passive"))
      (node (ref "U$5") (pin "P$1") (pinfunction "AIN-_P$1") (pintype "bidirectional"))
    )
    (net (code "5") (name "/AGND") (class "Default")
      (node (ref "C10") (pin "2") (pinfunction "2_2") (pintype "passive"))
      (node (ref "C41") (pin "2") (pinfunction "2_2") (pintype "passive"))
      (node (ref "C6") (pin "2") (pinfunction "2_2") (pintype "passive"))
      (node (ref "C7") (pin "2") (pinfunction "2_2") (pintype "passive"))
      (node (ref "C9") (pin "2") (pinfunction "2_2") (pintype "passive"))
      (node (ref "IC1") (pin "1") (pinfunction "AGND_1") (pintype "power_in"))
      (node (ref "IC1") (pin "16") (pinfunction "AGND_16") (pintype "power_in"))
      (node (ref "IC1") (pin "17") (pinfunction "AGND_17") (pintype "power_in"))
      (node (ref "IC1") (pin "32") (pinfunction "AGND_32") (pintype "power_in"))
      (node (ref "IC1") (pin "33") (pinfunction "ANGD_33") (pintype "power_in"))
      (node (ref "IC1") (pin "48") (pinfunction "ANGD_48") (pintype "power_in"))
      (node (ref "IC1") (pin "49") (pinfunction "ANGD_49") (pintype "power_in"))
      (node (ref "IC1") (pin "58") (pinfunction "ANGD_58") (pintype "power_in"))
      (node (ref "IC1") (pin "64") (pinfunction "ANGD_64") (pintype "power_in"))
      (node (ref "IC13") (pin "2") (pinfunction "GND_2") (pintype "bidirectional"))
      (node (ref "JP2") (pin "2") (pinfunction "2_2") (pintype "passive"))
      (node (ref "JP6") (pin "2") (pinfunction "2_2") (pintype "passive"))
      (node (ref "R2") (pin "3") (pinfunction "3_3") (pintype "passive"))
      (node (ref "TP19") (pin "TP") (pinfunction "TP_TP") (pintype "input"))
      (node (ref "TP22") (pin "TP") (pinfunction "TP_TP") (pintype "input"))
    )
    (net (code "6") (name "/AVDD") (class "Default")
      (node (ref "C10") (pin "1") (pinfunction "1_1") (pintype "passive"))
      (node (ref "C41") (pin "1") (pinfunction "1_1") (pintype "passive"))
      (node (ref "C6") (pin "1") (pinfunction "1_1") (pintype "passive"))
      (node (ref "C9") (pin "1") (pinfunction "1_1") (pintype "passive"))
      (node (ref "IC1") (pin "62") (pinfunction "AVDD_62") (pintype "power_in"))
      (node (ref "IC13") (pin "5") (pinfunction "VREF_5") (pintype "bidirectional"))
      (node (ref "R1") (pin "1") (pinfunction "1_1") (pintype "passive"))
      (node (ref "TP7") (pin "TP") (pinfunction "TP_TP") (pintype "input"))
    )
    (net (code "7") (name "/BASELINE") (class "Default")
      (node (ref "IC1") (pin "56") (pinfunction "BASELINE_56") (pintype "output"))
      (node (ref "JP19") (pin "1") (pinfunction "1_1") (pintype "passive"))
      (node (ref "TP10") (pin "TP") (pinfunction "TP_TP") (pintype "input"))
    )
    (net (code "8") (name "/CAP_PRECHAR") (class "Default")
      (node (ref "C38") (pin "2") (pinfunction "2_2") (pintype "passive"))
      (node (ref "IC1") (pin "14") (pinfunction "CAP_PRECHARGE_EXT_14") (pintype "input"))
      (node (ref "TP21") (pin "TP") (pinfunction "TP_TP") (pintype "input"))
    )
    (net (code "9") (name "/CAP_PRECHAR_1") (class "Default")
      (node (ref "C57") (pin "1") (pinfunction "1_1") (pintype "passive"))
      (node (ref "IC21") (pin "12") (pinfunction "D4_12") (pintype "bidirectional"))
      (node (ref "JP1") (pin "1") (pinfunction "1_1") (pintype "passive"))
    )
    (net (code "10") (name "/CLK") (class "Default")
      (node (ref "IC1") (pin "20") (pinfunction "CLK_20") (pintype "bidirectional"))
      (node (ref "R30") (pin "1") (pinfunction "1_1") (pintype "passive"))
      (node (ref "R31") (pin "2") (pinfunction "2_2") (pintype "passive"))
    )
    (net (code "11") (name "/CLK_ADC1") (class "Default")
      (node (ref "IC22") (pin "P$10") (pinfunction "SCLK_P$10") (pintype "bidirectional"))
      (node (ref "J1") (pin "A45") (pinfunction "A45_A45") (pintype "bidirectional"))
    )
    (net (code "12") (name "/CLK_ADC2") (class "Default")
      (node (ref "J1") (pin "A16") (pinfunction "A16_A16") (pintype "bidirectional"))
      (node (ref "U$5") (pin "P$10") (pinfunction "SCLK_P$10") (pintype "bidirectional"))
    )
    (net (code "13") (name "/CLK_DAC") (class "Default")
      (node (ref "IC23") (pin "10") (pinfunction "SCLK_10") (pintype "bidirectional"))
      (node (ref "J1") (pin "A19") (pinfunction "A19_A19") (pintype "bidirectional"))
    )
    (net (code "14") (name "/CLK_PRECH1") (class "Default")
      (node (ref "IC1") (pin "9") (pinfunction "CLK_PRECH1_9") (pintype "bidirectional"))
      (node (ref "R40") (pin "1") (pinfunction "1_1") (pintype "passive"))
      (node (ref "R41") (pin "2") (pinfunction "2_2") (pintype "passive"))
    )
    (net (code "15") (name "/CLK_PRECH1_T") (class "Default")
      (node (ref "J1") (pin "A42") (pinfunction "A42_A42") (pintype "bidirectional"))
      (node (ref "R40") (pin "2") (pinfunction "2_2") (pintype "passive"))
    )
    (net (code "16") (name "/CLK_PRECH2") (class "Default")
      (node (ref "IC1") (pin "10") (pinfunction "CLK_PRECH2_10") (pintype "bidirectional"))
      (node (ref "R42") (pin "1") (pinfunction "1_1") (pintype "passive"))
      (node (ref "R43") (pin "2") (pinfunction "2_2") (pintype "passive"))
    )
    (net (code "17") (name "/CLK_PRECH2_T") (class "Default")
      (node (ref "J1") (pin "A40") (pinfunction "A40_A40") (pintype "bidirectional"))
      (node (ref "R42") (pin "2") (pinfunction "2_2") (pintype "passive"))
    )
    (net (code "18") (name "/CLK_REF") (class "Default")
      (node (ref "IC18") (pin "4") (pinfunction "CLK_4") (pintype "bidirectional"))
      (node (ref "IC19") (pin "4") (pinfunction "CLK_4") (pintype "bidirectional"))
      (node (ref "IC20") (pin "4") (pinfunction "CLK_4") (pintype "bidirectional"))
      (node (ref "J1") (pin "A8") (pinfunction "A8_A8") (pintype "bidirectional"))
    )
    (net (code "19") (name "/CLK_T") (class "Default")
      (node (ref "J1") (pin "A32") (pinfunction "A32_A32") (pintype "bidirectional"))
      (node (ref "R30") (pin "2") (pinfunction "2_2") (pintype "passive"))
    )
    (net (code "20") (name "/CS_B0") (class "Default")
      (node (ref "IC1") (pin "41") (pinfunction "CS_B0_41") (pintype "bidirectional"))
      (node (ref "R14") (pin "1") (pinfunction "1_1") (pintype "passive"))
      (node (ref "R15") (pin "2") (pinfunction "2_2") (pintype "passive"))
    )
    (net (code "21") (name "/CS_B0_T") (class "Default")
      (node (ref "J1") (pin "A26") (pinfunction "A26_A26") (pintype "bidirectional"))
      (node (ref "R14") (pin "2") (pinfunction "2_2") (pintype "passive"))
    )
    (net (code "22") (name "/CS_B1") (class "Default")
      (node (ref "IC1") (pin "42") (pinfunction "CS_B1_42") (pintype "bidirectional"))
      (node (ref "R16") (pin "1") (pinfunction "1_1") (pintype "passive"))
      (node (ref "R17") (pin "2") (pinfunction "2_2") (pintype "passive"))
    )
    (net (code "23") (name "/CS_B1_T") (class "Default")
      (node (ref "J1") (pin "A28") (pinfunction "A28_A28") (pintype "bidirectional"))
      (node (ref "R16") (pin "2") (pinfunction "2_2") (pintype "passive"))
    )
    (net (code "24") (name "/CS_B2") (class "Default")
      (node (ref "IC1") (pin "43") (pinfunction "CS_B2_43") (pintype "bidirectional"))
      (node (ref "R18") (pin "1") (pinfunction "1_1") (pintype "passive"))
      (node (ref "R19") (pin "2") (pinfunction "2_2") (pintype "passive"))
    )
    (net (code "25") (name "/CS_B2_T") (class "Default")
      (node (ref "J1") (pin "A30") (pinfunction "A30_A30") (pintype "bidirectional"))
      (node (ref "R18") (pin "2") (pinfunction "2_2") (pintype "passive"))
    )
    (net (code "26") (name "/CS_B3") (class "Default")
      (node (ref "IC1") (pin "44") (pinfunction "CS_B3_44") (pintype "bidirectional"))
      (node (ref "R20") (pin "1") (pinfunction "1_1") (pintype "passive"))
      (node (ref "R21") (pin "2") (pinfunction "2_2") (pintype "passive"))
    )
    (net (code "27") (name "/CS_B3_T") (class "Default")
      (node (ref "J1") (pin "A34") (pinfunction "A34_A34") (pintype "bidirectional"))
      (node (ref "R20") (pin "2") (pinfunction "2_2") (pintype "passive"))
    )
    (net (code "28") (name "/CS_B4") (class "Default")
      (node (ref "IC1") (pin "45") (pinfunction "CS_B4_45") (pintype "bidirectional"))
      (node (ref "R22") (pin "1") (pinfunction "1_1") (pintype "passive"))
      (node (ref "R23") (pin "2") (pinfunction "2_2") (pintype "passive"))
    )
    (net (code "29") (name "/CS_B4_T") (class "Default")
      (node (ref "J1") (pin "A36") (pinfunction "A36_A36") (pintype "bidirectional"))
      (node (ref "R22") (pin "2") (pinfunction "2_2") (pintype "passive"))
    )
    (net (code "30") (name "/CS_B5") (class "Default")
      (node (ref "IC1") (pin "46") (pinfunction "CS_B5_46") (pintype "bidirectional"))
      (node (ref "R24") (pin "1") (pinfunction "1_1") (pintype "passive"))
      (node (ref "R25") (pin "2") (pinfunction "2_2") (pintype "passive"))
    )
    (net (code "31") (name "/CS_B5_T") (class "Default")
      (node (ref "J1") (pin "A38") (pinfunction "A38_A38") (pintype "bidirectional"))
      (node (ref "R24") (pin "2") (pinfunction "2_2") (pintype "passive"))
    )
    (net (code "32") (name "/CS_REF_1") (class "Default")
      (node (ref "IC18") (pin "6") (pinfunction "CS~{}_6") (pintype "bidirectional"))
      (node (ref "J1") (pin "A12") (pinfunction "A12_A12") (pintype "bidirectional"))
    )
    (net (code "33") (name "/CS_REF_2") (class "Default")
      (node (ref "IC19") (pin "6") (pinfunction "CS~{}_6") (pintype "bidirectional"))
      (node (ref "J1") (pin "A10") (pinfunction "A10_A10") (pintype "bidirectional"))
    )
    (net (code "34") (name "/CS_REF_3") (class "Default")
      (node (ref "IC20") (pin "6") (pinfunction "CS~{}_6") (pintype "bidirectional"))
      (node (ref "J1") (pin "A7") (pinfunction "A7_A7") (pintype "bidirectional"))
    )
    (net (code "35") (name "/DGND") (class "Default")
      (node (ref "C11") (pin "2") (pinfunction "2_2") (pintype "passive"))
      (node (ref "C12") (pin "2") (pinfunction "2_2") (pintype "passive"))
      (node (ref "C13") (pin "2") (pinfunction "2_2") (pintype "passive"))
      (node (ref "C40") (pin "2") (pinfunction "2_2") (pintype "passive"))
      (node (ref "C5") (pin "2") (pinfunction "2_2") (pintype "passive"))
      (node (ref "IC1") (pin "28") (pinfunction "DGND_28") (pintype "power_in"))
      (node (ref "IC10") (pin "2") (pinfunction "GND_2") (pintype "bidirectional"))
      (node (ref "JP6") (pin "1") (pinfunction "1_1") (pintype "passive"))
      (node (ref "TP23") (pin "TP") (pinfunction "TP_TP") (pintype "input"))
      (node (ref "TP29") (pin "TP") (pinfunction "TP_TP") (pintype "input"))
    )
    (net (code "36") (name "/DVDD") (class "Default")
      (node (ref "C11") (pin "1") (pinfunction "1_1") (pintype "passive"))
      (node (ref "C12") (pin "1") (pinfunction "1_1") (pintype "passive"))
      (node (ref "C13") (pin "1") (pinfunction "1_1") (pintype "passive"))
      (node (ref "C40") (pin "1") (pinfunction "1_1") (pintype "passive"))
      (node (ref "IC1") (pin "27") (pinfunction "DVDD_27") (pintype "power_in"))
      (node (ref "IC10") (pin "5") (pinfunction "VREF_5") (pintype "bidirectional"))
      (node (ref "TP8") (pin "TP") (pinfunction "TP_TP") (pintype "input"))
    )
    (net (code "37") (name "/GND") (class "Default")
      (node (ref "C1") (pin "2") (pinfunction "2_2") (pintype "passive"))
      (node (ref "C14") (pin "2") (pinfunction "2_2") (pintype "passive"))
      (node (ref "C15") (pin "2") (pinfunction "2_2") (pintype "passive"))
      (node (ref "C16") (pin "2") (pinfunction "2_2") (pintype "passive"))
      (node (ref "C17") (pin "2") (pinfunction "2_2") (pintype "passive"))
      (node (ref "C18") (pin "2") (pinfunction "2_2") (pintype "passive"))
      (node (ref "C19") (pin "2") (pinfunction "2_2") (pintype "passive"))
      (node (ref "C2") (pin "2") (pinfunction "2_2") (pintype "passive"))
      (node (ref "C20") (pin "2") (pinfunction "2_2") (pintype "passive"))
      (node (ref "C21") (pin "2") (pinfunction "2_2") (pintype "passive"))
      (node (ref "C22") (pin "2") (pinfunction "2_2") (pintype "passive"))
      (node (ref "C23") (pin "2") (pinfunction "2_2") (pintype "passive"))
      (node (ref "C24") (pin "2") (pinfunction "2_2") (pintype "passive"))
      (node (ref "C25") (pin "2") (pinfunction "2_2") (pintype "passive"))
      (node (ref "C26") (pin "2") (pinfunction "2_2") (pintype "passive"))
      (node (ref "C27") (pin "2") (pinfunction "2_2") (pintype "passive"))
      (node (ref "C28") (pin "2") (pinfunction "2_2") (pintype "passive"))
      (node (ref "C29") (pin "2") (pinfunction "2_2") (pintype "passive"))
      (node (ref "C3") (pin "2") (pinfunction "2_2") (pintype "passive"))
      (node (ref "C30") (pin "2") (pinfunction "2_2") (pintype "passive"))
      (node (ref "C31") (pin "2") (pinfunction "2_2") (pintype "passive"))
      (node (ref "C32") (pin "2") (pinfunction "2_2") (pintype "passive"))
      (node (ref "C33") (pin "2") (pinfunction "2_2") (pintype "passive"))
      (node (ref "C34") (pin "2") (pinfunction "2_2") (pintype "passive"))
      (node (ref "C35") (pin "2") (pinfunction "2_2") (pintype "passive"))
      (node (ref "C39") (pin "1") (pinfunction "1_1") (pintype "passive"))
      (node (ref "C4") (pin "2") (pinfunction "2_2") (pintype "passive"))
      (node (ref "C42") (pin "2") (pinfunction "2_2") (pintype "passive"))
      (node (ref "C43") (pin "2") (pinfunction "2_2") (pintype "passive"))
      (node (ref "C44") (pin "2") (pinfunction "2_2") (pintype "passive"))
      (node (ref "C45") (pin "2") (pinfunction "2_2") (pintype "passive"))
      (node (ref "C46") (pin "2") (pinfunction "2_2") (pintype "passive"))
      (node (ref "C47") (pin "2") (pinfunction "2_2") (pintype "passive"))
      (node (ref "C48") (pin "2") (pinfunction "2_2") (pintype "passive"))
      (node (ref "C49") (pin "2") (pinfunction "2_2") (pintype "passive"))
      (node (ref "C52") (pin "2") (pinfunction "2_2") (pintype "passive"))
      (node (ref "C53") (pin "2") (pinfunction "2_2") (pintype "passive"))
      (node (ref "C54") (pin "2") (pinfunction "2_2") (pintype "passive"))
      (node (ref "C55") (pin "2") (pinfunction "2_2") (pintype "passive"))
      (node (ref "C56") (pin "2") (pinfunction "2_2") (pintype "passive"))
      (node (ref "C57") (pin "2") (pinfunction "2_2") (pintype "passive"))
      (node (ref "C8") (pin "2") (pinfunction "2_2") (pintype "passive"))
      (node (ref "IC11") (pin "2") (pinfunction "GND_2") (pintype "passive"))
      (node (ref "IC16") (pin "2") (pinfunction "GND_2") (pintype "bidirectional"))
      (node (ref "IC17") (pin "2") (pinfunction "GND_2") (pintype "bidirectional"))
      (node (ref "IC18") (pin "3") (pinfunction "GND_3") (pintype "bidirectional"))
      (node (ref "IC18") (pin "8") (pinfunction "A_8") (pintype "bidirectional"))
      (node (ref "IC19") (pin "3") (pinfunction "GND_3") (pintype "bidirectional"))
      (node (ref "IC19") (pin "8") (pinfunction "A_8") (pintype "bidirectional"))
      (node (ref "IC2") (pin "2") (pinfunction "GND_2") (pintype "bidirectional"))
      (node (ref "IC20") (pin "3") (pinfunction "GND_3") (pintype "bidirectional"))
      (node (ref "IC20") (pin "8") (pinfunction "A_8") (pintype "bidirectional"))
      (node (ref "IC21") (pin "10") (pinfunction "S3B_10") (pintype "bidirectional"))
      (node (ref "IC21") (pin "13") (pinfunction "S4B_13") (pintype "bidirectional"))
      (node (ref "IC21") (pin "8") (pinfunction "GND_8") (pintype "bidirectional"))
      (node (ref "IC22") (pin "P$3") (pinfunction "RGND_P$3") (pintype "bidirectional"))
      (node (ref "IC22") (pin "P$6") (pinfunction "GND_P$6") (pintype "bidirectional"))
      (node (ref "IC23") (pin "3") (pinfunction "GND_3") (pintype "bidirectional"))
      (node (ref "IC3") (pin "2") (pinfunction "GND_2") (pintype "bidirectional"))
      (node (ref "IC4") (pin "2") (pinfunction "GND_2") (pintype "bidirectional"))
      (node (ref "IC5") (pin "2") (pinfunction "GND_2") (pintype "bidirectional"))
      (node (ref "IC6") (pin "2") (pinfunction "GND_2") (pintype "bidirectional"))
      (node (ref "IC7") (pin "2") (pinfunction "GND_2") (pintype "bidirectional"))
      (node (ref "IC8") (pin "2") (pinfunction "GND_2") (pintype "bidirectional"))
      (node (ref "IC9") (pin "2") (pinfunction "GND_2") (pintype "passive"))
      (node (ref "J1") (pin "B10") (pinfunction "B10_B10") (pintype "bidirectional"))
      (node (ref "J1") (pin "B11") (pinfunction "B11_B11") (pintype "bidirectional"))
      (node (ref "J1") (pin "B12") (pinfunction "B12_B12") (pintype "bidirectional"))
      (node (ref "J1") (pin "B13") (pinfunction "B13_B13") (pintype "bidirectional"))
      (node (ref "J1") (pin "B14") (pinfunction "B14_B14") (pintype "bidirectional"))
      (node (ref "J1") (pin "B15") (pinfunction "B15_B15") (pintype "bidirectional"))
      (node (ref "J1") (pin "B16") (pinfunction "B16_B16") (pintype "bidirectional"))
      (node (ref "J1") (pin "B17") (pinfunction "B17_B17") (pintype "bidirectional"))
      (node (ref "J1") (pin "B18") (pinfunction "B18_B18") (pintype "bidirectional"))
      (node (ref "J1") (pin "B19") (pinfunction "B19_B19") (pintype "bidirectional"))
      (node (ref "J1") (pin "B2") (pinfunction "B2_B2") (pintype "bidirectional"))
      (node (ref "J1") (pin "B20") (pinfunction "B20_B20") (pintype "bidirectional"))
      (node (ref "J1") (pin "B21") (pinfunction "B21_B21") (pintype "bidirectional"))
      (node (ref "J1") (pin "B22") (pinfunction "B22_B22") (pintype "bidirectional"))
      (node (ref "J1") (pin "B23") (pinfunction "B23_B23") (pintype "bidirectional"))
      (node (ref "J1") (pin "B24") (pinfunction "B24_B24") (pintype "bidirectional"))
      (node (ref "J1") (pin "B25") (pinfunction "B25_B25") (pintype "bidirectional"))
      (node (ref "J1") (pin "B26") (pinfunction "B26_B26") (pintype "bidirectional"))
      (node (ref "J1") (pin "B27") (pinfunction "B27_B27") (pintype "bidirectional"))
      (node (ref "J1") (pin "B28") (pinfunction "B28_B28") (pintype "bidirectional"))
      (node (ref "J1") (pin "B29") (pinfunction "B29_B29") (pintype "bidirectional"))
      (node (ref "J1") (pin "B30") (pinfunction "B30_B30") (pintype "bidirectional"))
      (node (ref "J1") (pin "B31") (pinfunction "B31_B31") (pintype "bidirectional"))
      (node (ref "J1") (pin "B32") (pinfunction "B32_B32") (pintype "bidirectional"))
      (node (ref "J1") (pin "B33") (pinfunction "B33_B33") (pintype "bidirectional"))
      (node (ref "J1") (pin "B34") (pinfunction "B34_B34") (pintype "bidirectional"))
      (node (ref "J1") (pin "B35") (pinfunction "B35_B35") (pintype "bidirectional"))
      (node (ref "J1") (pin "B36") (pinfunction "B36_B36") (pintype "bidirectional"))
      (node (ref "J1") (pin "B37") (pinfunction "B37_B37") (pintype "bidirectional"))
      (node (ref "J1") (pin "B38") (pinfunction "B38_B38") (pintype "bidirectional"))
      (node (ref "J1") (pin "B39") (pinfunction "B39_B39") (pintype "bidirectional"))
      (node (ref "J1") (pin "B40") (pinfunction "B40_B40") (pintype "bidirectional"))
      (node (ref "J1") (pin "B41") (pinfunction "B41_B41") (pintype "bidirectional"))
      (node (ref "J1") (pin "B42") (pinfunction "B42_B42") (pintype "bidirectional"))
      (node (ref "J1") (pin "B43") (pinfunction "B43_B43") (pintype "bidirectional"))
      (node (ref "J1") (pin "B44") (pinfunction "B44_B44") (pintype "bidirectional"))
      (node (ref "J1") (pin "B45") (pinfunction "B45_B45") (pintype "bidirectional"))
      (node (ref "J1") (pin "B47") (pinfunction "B47_B47") (pintype "bidirectional"))
      (node (ref "J1") (pin "B5") (pinfunction "B5_B5") (pintype "bidirectional"))
      (node (ref "J1") (pin "B6") (pinfunction "B6_B6") (pintype "bidirectional"))
      (node (ref "J1") (pin "B7") (pinfunction "B7_B7") (pintype "bidirectional"))
      (node (ref "J1") (pin "B8") (pinfunction "B8_B8") (pintype "bidirectional"))
      (node (ref "J1") (pin "B9") (pinfunction "B9_B9") (pintype "bidirectional"))
      (node (ref "JP14") (pin "1") (pinfunction "1_1") (pintype "passive"))
      (node (ref "JP17") (pin "3") (pinfunction "P$3_3") (pintype "bidirectional"))
      (node (ref "JP2") (pin "1") (pinfunction "1_1") (pintype "passive"))
      (node (ref "R15") (pin "1") (pinfunction "1_1") (pintype "passive"))
      (node (ref "R17") (pin "1") (pinfunction "1_1") (pintype "passive"))
      (node (ref "R19") (pin "1") (pinfunction "1_1") (pintype "passive"))
      (node (ref "R21") (pin "1") (pinfunction "1_1") (pintype "passive"))
      (node (ref "R23") (pin "1") (pinfunction "1_1") (pintype "passive"))
      (node (ref "R25") (pin "1") (pinfunction "1_1") (pintype "passive"))
      (node (ref "R27") (pin "1") (pinfunction "1_1") (pintype "passive"))
      (node (ref "R29") (pin "1") (pinfunction "1_1") (pintype "passive"))
      (node (ref "R31") (pin "1") (pinfunction "1_1") (pintype "passive"))
      (node (ref "R33") (pin "1") (pinfunction "1_1") (pintype "passive"))
      (node (ref "R35") (pin "1") (pinfunction "1_1") (pintype "passive"))
      (node (ref "R37") (pin "1") (pinfunction "1_1") (pintype "passive"))
      (node (ref "R39") (pin "1") (pinfunction "1_1") (pintype "passive"))
      (node (ref "R4") (pin "3") (pinfunction "3_3") (pintype "passive"))
      (node (ref "R41") (pin "1") (pinfunction "1_1") (pintype "passive"))
      (node (ref "R43") (pin "1") (pinfunction "1_1") (pintype "passive"))
      (node (ref "R5") (pin "3") (pinfunction "3_3") (pintype "passive"))
      (node (ref "R6") (pin "3") (pinfunction "3_3") (pintype "passive"))
      (node (ref "R8") (pin "1") (pinfunction "1_1") (pintype "passive"))
      (node (ref "R9") (pin "1") (pinfunction "1_1") (pintype "passive"))
      (node (ref "TP18") (pin "TP") (pinfunction "TP_TP") (pintype "input"))
      (node (ref "TP31") (pin "TP") (pinfunction "TP_TP") (pintype "input"))
      (node (ref "TP32") (pin "TP") (pinfunction "TP_TP") (pintype "input"))
      (node (ref "TP33") (pin "TP") (pinfunction "TP_TP") (pintype "input"))
      (node (ref "TP34") (pin "TP") (pinfunction "TP_TP") (pintype "input"))
      (node (ref "TP35") (pin "TP") (pinfunction "TP_TP") (pintype "input"))
      (node (ref "TP36") (pin "TP") (pinfunction "TP_TP") (pintype "input"))
      (node (ref "TP38") (pin "TP") (pinfunction "TP_TP") (pintype "input"))
      (node (ref "U$5") (pin "P$3") (pinfunction "RGND_P$3") (pintype "bidirectional"))
      (node (ref "U$5") (pin "P$6") (pinfunction "GND_P$6") (pintype "bidirectional"))
    )
    (net (code "38") (name "/HOLD") (class "Default")
      (node (ref "IC1") (pin "37") (pinfunction "HOLD_37") (pintype "bidirectional"))
      (node (ref "R38") (pin "1") (pinfunction "1_1") (pintype "passive"))
      (node (ref "R39") (pin "2") (pinfunction "2_2") (pintype "passive"))
    )
    (net (code "39") (name "/HOLD_T") (class "Default")
      (node (ref "J1") (pin "A23") (pinfunction "A23_A23") (pintype "bidirectional"))
      (node (ref "R38") (pin "2") (pinfunction "2_2") (pintype "passive"))
    )
    (net (code "40") (name "/MUX_DAC_EN") (class "Default")
      (node (ref "IC21") (pin "15") (pinfunction "~{EN}_15") (pintype "bidirectional"))
      (node (ref "J1") (pin "A21") (pinfunction "A21_A21") (pintype "bidirectional"))
    )
    (net (code "41") (name "/MUX_DAC_SEL") (class "Default")
      (node (ref "IC21") (pin "1") (pinfunction "IN_1") (pintype "bidirectional"))
      (node (ref "J1") (pin "A20") (pinfunction "A20_A20") (pintype "bidirectional"))
    )
    (net (code "42") (name "/MUX_REF_1") (class "Default")
      (node (ref "IC2") (pin "6") (pinfunction "IN_6") (pintype "bidirectional"))
      (node (ref "J1") (pin "A13") (pinfunction "A13_A13") (pintype "bidirectional"))
    )
    (net (code "43") (name "/MUX_REF_2") (class "Default")
      (node (ref "IC3") (pin "6") (pinfunction "IN_6") (pintype "bidirectional"))
      (node (ref "J1") (pin "A11") (pinfunction "A11_A11") (pintype "bidirectional"))
    )
    (net (code "44") (name "/MUX_REF_3") (class "Default")
      (node (ref "IC4") (pin "6") (pinfunction "IN_6") (pintype "bidirectional"))
      (node (ref "J1") (pin "A9") (pinfunction "A9_A9") (pintype "bidirectional"))
    )
    (net (code "45") (name "/N$9") (class "Default")
      (node (ref "JP13") (pin "1") (pinfunction "1_1") (pintype "passive"))
      (node (ref "JP19") (pin "2") (pinfunction "2_2") (pintype "passive"))
    )
    (net (code "46") (name "/OP_MODE") (class "Default")
      (node (ref "IC1") (pin "11") (pinfunction "OP_MODE_11") (pintype "bidirectional"))
      (node (ref "R26") (pin "1") (pinfunction "1_1") (pintype "passive"))
      (node (ref "R27") (pin "2") (pinfunction "2_2") (pintype "passive"))
    )
    (net (code "47") (name "/OP_MODE_T") (class "Default")
      (node (ref "J1") (pin "A35") (pinfunction "A35_A35") (pintype "bidirectional"))
      (node (ref "R26") (pin "2") (pinfunction "2_2") (pintype "passive"))
    )
    (net (code "48") (name "/OUT_S") (class "Default")
      (node (ref "IC1") (pin "35") (pinfunction "OUT_S_35") (pintype "bidirectional"))
      (node (ref "R32") (pin "1") (pinfunction "1_1") (pintype "passive"))
      (node (ref "R33") (pin "2") (pinfunction "2_2") (pintype "passive"))
    )
    (net (code "49") (name "/OUT_S_T") (class "Default")
      (node (ref "J1") (pin "A22") (pinfunction "A22_A22") (pintype "bidirectional"))
      (node (ref "R32") (pin "2") (pinfunction "2_2") (pintype "passive"))
    )
    (net (code "50") (name "/POT_R1") (class "Default")
      (node (ref "JP4") (pin "3") (pinfunction "3_3") (pintype "passive"))
      (node (ref "R1") (pin "2") (pinfunction "2_2") (pintype "passive"))
      (node (ref "R1") (pin "3") (pinfunction "3_3") (pintype "passive"))
      (node (ref "TP27") (pin "TP") (pinfunction "TP_TP") (pintype "input"))
    )
    (net (code "51") (name "/POT_R2") (class "Default")
      (node (ref "JP4") (pin "1") (pinfunction "1_1") (pintype "passive"))
      (node (ref "R2") (pin "1") (pinfunction "1_1") (pintype "passive"))
      (node (ref "R2") (pin "2") (pinfunction "2_2") (pintype "passive"))
      (node (ref "TP28") (pin "TP") (pinfunction "TP_TP") (pintype "input"))
    )
    (net (code "52") (name "/POT_R4") (class "Default")
      (node (ref "IC2") (pin "3") (pinfunction "A1_3") (pintype "bidirectional"))
      (node (ref "R4") (pin "2") (pinfunction "2_2") (pintype "passive"))
      (node (ref "TP24") (pin "TP") (pinfunction "TP_TP") (pintype "input"))
    )
    (net (code "53") (name "/POT_R5") (class "Default")
      (node (ref "IC3") (pin "3") (pinfunction "A1_3") (pintype "bidirectional"))
      (node (ref "R5") (pin "2") (pinfunction "2_2") (pintype "passive"))
      (node (ref "TP25") (pin "TP") (pinfunction "TP_TP") (pintype "input"))
    )
    (net (code "54") (name "/POT_R6") (class "Default")
      (node (ref "IC4") (pin "3") (pinfunction "A1_3") (pintype "bidirectional"))
      (node (ref "R6") (pin "2") (pinfunction "2_2") (pintype "passive"))
      (node (ref "TP26") (pin "TP") (pinfunction "TP_TP") (pintype "input"))
    )
    (net (code "55") (name "/REFIN_DAC") (class "Default")
      (node (ref "C28") (pin "1") (pinfunction "1_1") (pintype "passive"))
      (node (ref "IC23") (pin "6") (pinfunction "REFIN_6") (pintype "bidirectional"))
      (node (ref "IC8") (pin "5") (pinfunction "VREF_5") (pintype "bidirectional"))
      (node (ref "TP15") (pin "TP") (pinfunction "TP_TP") (pintype "input"))
    )
    (net (code "56") (name "/REF_ADC") (class "Default")
      (node (ref "C31") (pin "1") (pinfunction "1_1") (pintype "passive"))
      (node (ref "TP17") (pin "TP") (pinfunction "TP_TP") (pintype "input"))
    )
    (net (code "57") (name "/REF_ADC1") (class "Default")
      (node (ref "C17") (pin "1") (pinfunction "1_1") (pintype "passive"))
      (node (ref "C18") (pin "1") (pinfunction "1_1") (pintype "passive"))
      (node (ref "IC22") (pin "P$2") (pinfunction "REF_P$2") (pintype "bidirectional"))
      (node (ref "TP39") (pin "TP") (pinfunction "TP_TP") (pintype "input"))
    )
    (net (code "58") (name "/REF_ADC2") (class "Default")
      (node (ref "C23") (pin "1") (pinfunction "1_1") (pintype "passive"))
      (node (ref "C24") (pin "1") (pinfunction "1_1") (pintype "passive"))
      (node (ref "TP40") (pin "TP") (pinfunction "TP_TP") (pintype "input"))
      (node (ref "U$5") (pin "P$2") (pinfunction "REF_P$2") (pintype "bidirectional"))
    )
    (net (code "59") (name "/RES_BIAS_EXT") (class "Default")
      (node (ref "IC1") (pin "6") (pinfunction "RES_BIAS_EXT_6") (pintype "bidirectional"))
      (node (ref "JP4") (pin "2") (pinfunction "2_2") (pintype "passive"))
    )
    (net (code "60") (name "/RST") (class "Default")
      (node (ref "IC1") (pin "38") (pinfunction "RST_38") (pintype "bidirectional"))
      (node (ref "R36") (pin "1") (pinfunction "1_1") (pintype "passive"))
      (node (ref "R37") (pin "2") (pinfunction "2_2") (pintype "passive"))
    )
    (net (code "61") (name "/RST_CSA") (class "Default")
      (node (ref "IC1") (pin "12") (pinfunction "RST_CSA_12") (pintype "bidirectional"))
      (node (ref "R28") (pin "1") (pinfunction "1_1") (pintype "passive"))
      (node (ref "R29") (pin "2") (pinfunction "2_2") (pintype "passive"))
    )
    (net (code "62") (name "/RST_CSA_T") (class "Default")
      (node (ref "J1") (pin "A33") (pinfunction "A33_A33") (pintype "bidirectional"))
      (node (ref "R28") (pin "2") (pinfunction "2_2") (pintype "passive"))
    )
    (net (code "63") (name "/RST_T") (class "Default")
      (node (ref "J1") (pin "A24") (pinfunction "A24_A24") (pintype "bidirectional"))
      (node (ref "R36") (pin "2") (pinfunction "2_2") (pintype "passive"))
    )
    (net (code "64") (name "/SDI_DAC") (class "Default")
      (node (ref "IC23") (pin "9") (pinfunction "DIN_9") (pintype "bidirectional"))
      (node (ref "J1") (pin "A18") (pinfunction "A18_A18") (pintype "bidirectional"))
    )
    (net (code "65") (name "/SDI_REF") (class "Default")
      (node (ref "IC18") (pin "5") (pinfunction "SDI_5") (pintype "bidirectional"))
      (node (ref "IC19") (pin "5") (pinfunction "SDI_5") (pintype "bidirectional"))
      (node (ref "IC20") (pin "5") (pinfunction "SDI_5") (pintype "bidirectional"))
      (node (ref "J1") (pin "A6") (pinfunction "A6_A6") (pintype "bidirectional"))
    )
    (net (code "66") (name "/SDO_ADC1") (class "Default")
      (node (ref "IC22") (pin "P$8") (pinfunction "DOUT_P$8") (pintype "bidirectional"))
      (node (ref "J1") (pin "A43") (pinfunction "A43_A43") (pintype "bidirectional"))
      (node (ref "R3") (pin "1") (pinfunction "1_1") (pintype "passive"))
    )
    (net (code "67") (name "/SDO_ADC2") (class "Default")
      (node (ref "J1") (pin "A14") (pinfunction "A14_A14") (pintype "bidirectional"))
      (node (ref "R7") (pin "1") (pinfunction "1_1") (pintype "passive"))
      (node (ref "U$5") (pin "P$8") (pinfunction "DOUT_P$8") (pintype "bidirectional"))
    )
    (net (code "68") (name "/SGN") (class "Default")
      (node (ref "IC1") (pin "39") (pinfunction "SGN_39") (pintype "bidirectional"))
      (node (ref "R34") (pin "1") (pinfunction "1_1") (pintype "passive"))
      (node (ref "R35") (pin "2") (pinfunction "2_2") (pintype "passive"))
    )
    (net (code "69") (name "/SGN_T") (class "Default")
      (node (ref "J1") (pin "A25") (pinfunction "A25_A25") (pintype "bidirectional"))
      (node (ref "R34") (pin "2") (pinfunction "2_2") (pintype "passive"))
    )
    (net (code "70") (name "/V0NDAC") (class "Default")
      (node (ref "IC21") (pin "5") (pinfunction "S2A_5") (pintype "bidirectional"))
      (node (ref "IC23") (pin "2") (pinfunction "VOUTB_2") (pintype "bidirectional"))
    )
    (net (code "71") (name "/V0PDAC") (class "Default")
      (node (ref "IC21") (pin "2") (pinfunction "S1A_2") (pintype "bidirectional"))
      (node (ref "IC23") (pin "1") (pinfunction "VOUTA_1") (pintype "bidirectional"))
    )
    (net (code "72") (name "/V1NDAC") (class "Default")
      (node (ref "C53") (pin "1") (pinfunction "1_1") (pintype "passive"))
      (node (ref "IC21") (pin "14") (pinfunction "S4A_14") (pintype "bidirectional"))
      (node (ref "IC23") (pin "5") (pinfunction "VOUTD_5") (pintype "bidirectional"))
    )
    (net (code "73") (name "/V1PDAC") (class "Default")
      (node (ref "C52") (pin "1") (pinfunction "1_1") (pintype "passive"))
      (node (ref "IC21") (pin "11") (pinfunction "S3A_11") (pintype "bidirectional"))
      (node (ref "IC23") (pin "4") (pinfunction "VOUTC_4") (pintype "bidirectional"))
    )
    (net (code "74") (name "/VDD") (class "Default")
      (node (ref "C1") (pin "1") (pinfunction "1_1") (pintype "passive"))
      (node (ref "C15") (pin "1") (pinfunction "1_1") (pintype "passive"))
      (node (ref "C16") (pin "1") (pinfunction "1_1") (pintype "passive"))
      (node (ref "C19") (pin "1") (pinfunction "1_1") (pintype "passive"))
      (node (ref "C2") (pin "1") (pinfunction "1_1") (pintype "passive"))
      (node (ref "C20") (pin "1") (pinfunction "1_1") (pintype "passive"))
      (node (ref "C25") (pin "1") (pinfunction "1_1") (pintype "passive"))
      (node (ref "C3") (pin "1") (pinfunction "1_1") (pintype "passive"))
      (node (ref "C30") (pin "1") (pinfunction "1_1") (pintype "passive"))
      (node (ref "C39") (pin "2") (pinfunction "2_2") (pintype "passive"))
      (node (ref "C4") (pin "1") (pinfunction "1_1") (pintype "passive"))
      (node (ref "C44") (pin "1") (pinfunction "1_1") (pintype "passive"))
      (node (ref "IC11") (pin "3") (pinfunction "VO_3") (pintype "passive"))
      (node (ref "IC16") (pin "3") (pinfunction "EN_3") (pintype "bidirectional"))
      (node (ref "IC16") (pin "4") (pinfunction "VIN_4") (pintype "bidirectional"))
      (node (ref "IC17") (pin "3") (pinfunction "EN_3") (pintype "bidirectional"))
      (node (ref "IC17") (pin "4") (pinfunction "VIN_4") (pintype "bidirectional"))
      (node (ref "IC18") (pin "2") (pinfunction "VDD_2") (pintype "bidirectional"))
      (node (ref "IC19") (pin "2") (pinfunction "VDD_2") (pintype "bidirectional"))
      (node (ref "IC2") (pin "5") (pinfunction "VCC_5") (pintype "bidirectional"))
      (node (ref "IC20") (pin "2") (pinfunction "VDD_2") (pintype "bidirectional"))
      (node (ref "IC21") (pin "16") (pinfunction "VDD_16") (pintype "bidirectional"))
      (node (ref "IC22") (pin "P$4") (pinfunction "VDD_P$4") (pintype "bidirectional"))
      (node (ref "IC23") (pin "8") (pinfunction "VDD_8") (pintype "bidirectional"))
      (node (ref "IC3") (pin "5") (pinfunction "VCC_5") (pintype "bidirectional"))
      (node (ref "IC4") (pin "5") (pinfunction "VCC_5") (pintype "bidirectional"))
      (node (ref "IC5") (pin "3") (pinfunction "EN_3") (pintype "bidirectional"))
      (node (ref "IC5") (pin "4") (pinfunction "VIN_4") (pintype "bidirectional"))
      (node (ref "IC6") (pin "3") (pinfunction "EN_3") (pintype "bidirectional"))
      (node (ref "IC6") (pin "4") (pinfunction "VIN_4") (pintype "bidirectional"))
      (node (ref "IC7") (pin "3") (pinfunction "EN_3") (pintype "bidirectional"))
      (node (ref "IC7") (pin "4") (pinfunction "VIN_4") (pintype "bidirectional"))
      (node (ref "IC8") (pin "3") (pinfunction "EN_3") (pintype "bidirectional"))
      (node (ref "IC8") (pin "4") (pinfunction "VIN_4") (pintype "bidirectional"))
      (node (ref "TP5") (pin "TP") (pinfunction "TP_TP") (pintype "input"))
      (node (ref "U$5") (pin "P$4") (pinfunction "VDD_P$4") (pintype "bidirectional"))
    )
    (net (code "75") (name "/VDD2") (class "Default")
      (node (ref "C46") (pin "1") (pinfunction "1_1") (pintype "passive"))
      (node (ref "C5") (pin "1") (pinfunction "1_1") (pintype "passive"))
      (node (ref "C7") (pin "1") (pinfunction "1_1") (pintype "passive"))
      (node (ref "IC10") (pin "3") (pinfunction "EN_3") (pintype "bidirectional"))
      (node (ref "IC10") (pin "4") (pinfunction "VIN_4") (pintype "bidirectional"))
      (node (ref "IC13") (pin "3") (pinfunction "EN_3") (pintype "bidirectional"))
      (node (ref "IC13") (pin "4") (pinfunction "VIN_4") (pintype "bidirectional"))
      (node (ref "IC9") (pin "3") (pinfunction "VO_3") (pintype "passive"))
      (node (ref "TP6") (pin "TP") (pinfunction "TP_TP") (pintype "input"))
    )
    (net (code "76") (name "/VDD_REF_1") (class "Default")
      (node (ref "C26") (pin "1") (pinfunction "1_1") (pintype "passive"))
      (node (ref "IC18") (pin "7") (pinfunction "B_7") (pintype "bidirectional"))
      (node (ref "IC5") (pin "5") (pinfunction "VREF_5") (pintype "bidirectional"))
      (node (ref "R4") (pin "1") (pinfunction "1_1") (pintype "passive"))
      (node (ref "TP41") (pin "TP") (pinfunction "TP_TP") (pintype "input"))
    )
    (net (code "77") (name "/VDD_REF_2") (class "Default")
      (node (ref "C27") (pin "1") (pinfunction "1_1") (pintype "passive"))
      (node (ref "IC19") (pin "7") (pinfunction "B_7") (pintype "bidirectional"))
      (node (ref "IC6") (pin "5") (pinfunction "VREF_5") (pintype "bidirectional"))
      (node (ref "R5") (pin "1") (pinfunction "1_1") (pintype "passive"))
      (node (ref "TP42") (pin "TP") (pinfunction "TP_TP") (pintype "input"))
    )
    (net (code "78") (name "/VDD_REF_3") (class "Default")
      (node (ref "C35") (pin "1") (pinfunction "1_1") (pintype "passive"))
      (node (ref "IC20") (pin "7") (pinfunction "B_7") (pintype "bidirectional"))
      (node (ref "IC7") (pin "5") (pinfunction "VREF_5") (pintype "bidirectional"))
      (node (ref "R6") (pin "1") (pinfunction "1_1") (pintype "passive"))
      (node (ref "TP43") (pin "TP") (pinfunction "TP_TP") (pintype "input"))
    )
    (net (code "79") (name "/VDD_SUPPLY_1") (class "Default")
      (node (ref "C43") (pin "1") (pinfunction "1_1") (pintype "passive"))
      (node (ref "IC11") (pin "1") (pinfunction "VI_1") (pintype "input"))
      (node (ref "JP5") (pin "1") (pinfunction "1_1") (pintype "passive"))
      (node (ref "TP1") (pin "TP") (pinfunction "TP_TP") (pintype "input"))
    )
    (net (code "80") (name "/VDD_SUPPLY_2") (class "Default")
      (node (ref "C45") (pin "1") (pinfunction "1_1") (pintype "passive"))
      (node (ref "IC9") (pin "1") (pinfunction "VI_1") (pintype "input"))
      (node (ref "JP8") (pin "1") (pinfunction "1_1") (pintype "passive"))
      (node (ref "TP3") (pin "TP") (pinfunction "TP_TP") (pintype "input"))
    )
    (net (code "81") (name "/VDD_SUPPLY_IN_1") (class "Default")
      (node (ref "IC12") (pin "8") (pinfunction "V+_8") (pintype "bidirectional"))
      (node (ref "IC14") (pin "8") (pinfunction "V+_8") (pintype "bidirectional"))
      (node (ref "JP17") (pin "1") (pinfunction "P$1_1") (pintype "bidirectional"))
      (node (ref "JP5") (pin "2") (pinfunction "2_2") (pintype "passive"))
      (node (ref "TP2") (pin "TP") (pinfunction "TP_TP") (pintype "input"))
    )
    (net (code "82") (name "/VDD_SUPPLY_IN_2") (class "Default")
      (node (ref "JP17") (pin "2") (pinfunction "P$2_2") (pintype "bidirectional"))
      (node (ref "JP8") (pin "2") (pinfunction "2_2") (pintype "passive"))
      (node (ref "TP4") (pin "TP") (pinfunction "TP_TP") (pintype "input"))
    )
    (net (code "83") (name "/VI+_FIL") (class "Default")
      (node (ref "IC1") (pin "22") (pinfunction "VI+_FIL_22") (pintype "input"))
      (node (ref "JP11") (pin "2") (pinfunction "2_2") (pintype "passive"))
    )
    (net (code "84") (name "/VI+_FIL_DAC") (class "Default")
      (node (ref "C54") (pin "1") (pinfunction "1_1") (pintype "passive"))
      (node (ref "IC21") (pin "4") (pinfunction "D1_4") (pintype "bidirectional"))
      (node (ref "JP11") (pin "1") (pinfunction "1_1") (pintype "passive"))
    )
    (net (code "85") (name "/VI-_FIL") (class "Default")
      (node (ref "IC1") (pin "23") (pinfunction "VI-_FIL_23") (pintype "input"))
      (node (ref "JP12") (pin "2") (pinfunction "2_2") (pintype "passive"))
    )
    (net (code "86") (name "/VI-_FIL_DAC") (class "Default")
      (node (ref "C55") (pin "1") (pinfunction "1_1") (pintype "passive"))
      (node (ref "IC21") (pin "7") (pinfunction "D2_7") (pintype "bidirectional"))
      (node (ref "JP12") (pin "1") (pinfunction "1_1") (pintype "passive"))
    )
    (net (code "87") (name "/VICM") (class "Default")
      (node (ref "IC1") (pin "40") (pinfunction "VICM_40") (pintype "input"))
      (node (ref "IC21") (pin "3") (pinfunction "S1B_3") (pintype "bidirectional"))
      (node (ref "IC21") (pin "6") (pinfunction "S2B_6") (pintype "bidirectional"))
      (node (ref "JP15") (pin "2") (pinfunction "2_2") (pintype "passive"))
      (node (ref "TP12") (pin "TP") (pinfunction "TP_TP") (pintype "input"))
    )
    (net (code "88") (name "/VICM_BUFF") (class "Default")
      (node (ref "C32") (pin "1") (pinfunction "1_1") (pintype "passive"))
      (node (ref "IC12") (pin "1") (pinfunction "OUTA_1") (pintype "bidirectional"))
      (node (ref "IC12") (pin "2") (pinfunction "-INA_2") (pintype "bidirectional"))
      (node (ref "JP15") (pin "1") (pinfunction "1_1") (pintype "passive"))
    )
    (net (code "89") (name "/VICM_MUX") (class "Default")
      (node (ref "C47") (pin "1") (pinfunction "1_1") (pintype "passive"))
      (node (ref "IC12") (pin "3") (pinfunction "+INA_3") (pintype "bidirectional"))
      (node (ref "IC3") (pin "4") (pinfunction "B_4") (pintype "bidirectional"))
      (node (ref "JP15") (pin "3") (pinfunction "3_3") (pintype "passive"))
      (node (ref "TP11") (pin "TP") (pinfunction "TP_TP") (pintype "input"))
    )
    (net (code "90") (name "/VIN_CSA") (class "Default")
      (node (ref "IC1") (pin "15") (pinfunction "VIN_CSA_15") (pintype "input"))
      (node (ref "JP1") (pin "3") (pinfunction "3_3") (pintype "passive"))
      (node (ref "JP10") (pin "2") (pinfunction "2_2") (pintype "passive"))
      (node (ref "TP20") (pin "TP") (pinfunction "TP_TP") (pintype "input"))
    )
    (net (code "91") (name "/VIN_CSA_1") (class "Default")
      (node (ref "C36") (pin "1") (pinfunction "1_1") (pintype "passive"))
      (node (ref "C56") (pin "1") (pinfunction "1_1") (pintype "passive"))
      (node (ref "IC21") (pin "9") (pinfunction "D3_9") (pintype "bidirectional"))
      (node (ref "JP9") (pin "1") (pinfunction "1_1") (pintype "passive"))
    )
    (net (code "92") (name "/VL_ADC") (class "Default")
      (node (ref "C14") (pin "1") (pinfunction "1_1") (pintype "passive"))
      (node (ref "C21") (pin "1") (pinfunction "1_1") (pintype "passive"))
      (node (ref "C22") (pin "1") (pinfunction "1_1") (pintype "passive"))
      (node (ref "C29") (pin "1") (pinfunction "1_1") (pintype "passive"))
      (node (ref "C8") (pin "1") (pinfunction "1_1") (pintype "passive"))
      (node (ref "IC16") (pin "5") (pinfunction "VREF_5") (pintype "bidirectional"))
      (node (ref "IC22") (pin "P$7") (pinfunction "VL_P$7") (pintype "bidirectional"))
      (node (ref "R3") (pin "2") (pinfunction "2_2") (pintype "passive"))
      (node (ref "R7") (pin "2") (pinfunction "2_2") (pintype "passive"))
      (node (ref "TP16") (pin "TP") (pinfunction "TP_TP") (pintype "input"))
      (node (ref "U$5") (pin "P$7") (pinfunction "VL_P$7") (pintype "bidirectional"))
    )
    (net (code "93") (name "/VO+_BP_FIL") (class "Default")
      (node (ref "IC1") (pin "24") (pinfunction "VO+_BP_FIL_24") (pintype "output"))
      (node (ref "JP3") (pin "3") (pinfunction "3_3") (pintype "passive"))
    )
    (net (code "94") (name "/VO+_CH") (class "Default")
      (node (ref "IC1") (pin "50") (pinfunction "VO+_CH_50") (pintype "input"))
      (node (ref "JP13") (pin "3") (pinfunction "3_3") (pintype "passive"))
    )
    (net (code "95") (name "/VO+_FIL") (class "Default")
      (node (ref "IC1") (pin "30") (pinfunction "VO+_FIL_30") (pintype "output"))
      (node (ref "JP3") (pin "1") (pinfunction "1_1") (pintype "passive"))
    )
    (net (code "96") (name "/VO-_BP_FIL") (class "Default")
      (node (ref "IC1") (pin "25") (pinfunction "VO-_BP_FIL_25") (pintype "output"))
      (node (ref "JP18") (pin "3") (pinfunction "3_3") (pintype "passive"))
    )
    (net (code "97") (name "/VO-_CH") (class "Default")
      (node (ref "IC1") (pin "52") (pinfunction "VO-_CH_52") (pintype "input"))
      (node (ref "JP14") (pin "3") (pinfunction "3_3") (pintype "passive"))
    )
    (net (code "98") (name "/VO-_FIL") (class "Default")
      (node (ref "IC1") (pin "31") (pinfunction "VO-_FIL_31") (pintype "output"))
      (node (ref "JP18") (pin "1") (pinfunction "1_1") (pintype "passive"))
    )
    (net (code "99") (name "/VOCM") (class "Default")
      (node (ref "IC1") (pin "34") (pinfunction "VOCM_AUX_34") (pintype "input"))
      (node (ref "IC1") (pin "36") (pinfunction "VOCM_36") (pintype "input"))
      (node (ref "JP16") (pin "2") (pinfunction "2_2") (pintype "passive"))
      (node (ref "TP14") (pin "TP") (pinfunction "TP_TP") (pintype "input"))
    )
    (net (code "100") (name "/VOCM_1") (class "Default")
      (node (ref "C49") (pin "1") (pinfunction "1_1") (pintype "passive"))
      (node (ref "IC14") (pin "3") (pinfunction "+INA_3") (pintype "bidirectional"))
      (node (ref "IC2") (pin "4") (pinfunction "B_4") (pintype "bidirectional"))
      (node (ref "JP7") (pin "3") (pinfunction "3_3") (pintype "passive"))
      (node (ref "TP30") (pin "TP") (pinfunction "TP_TP") (pintype "input"))
    )
    (net (code "101") (name "/VOCM_BUFF") (class "Default")
      (node (ref "C33") (pin "1") (pinfunction "1_1") (pintype "passive"))
      (node (ref "IC12") (pin "6") (pinfunction "-INB_6") (pintype "bidirectional"))
      (node (ref "IC12") (pin "7") (pinfunction "OUTB_7") (pintype "bidirectional"))
      (node (ref "JP16") (pin "1") (pinfunction "1_1") (pintype "passive"))
    )
    (net (code "102") (name "/VOCM_MUX") (class "Default")
      (node (ref "C48") (pin "1") (pinfunction "1_1") (pintype "passive"))
      (node (ref "IC12") (pin "5") (pinfunction "+INB_5") (pintype "bidirectional"))
      (node (ref "IC4") (pin "4") (pinfunction "B_4") (pintype "bidirectional"))
      (node (ref "JP16") (pin "3") (pinfunction "3_3") (pintype "passive"))
      (node (ref "TP13") (pin "TP") (pinfunction "TP_TP") (pintype "input"))
    )
    (net (code "103") (name "/VOUT_CSA") (class "Default")
      (node (ref "IC1") (pin "54") (pinfunction "VOUT_CSA_54") (pintype "output"))
      (node (ref "JP19") (pin "3") (pinfunction "3_3") (pintype "passive"))
      (node (ref "TP9") (pin "TP") (pinfunction "TP_TP") (pintype "input"))
    )
    (net (code "104") (name "/VSS") (class "Default")
      (node (ref "IC12") (pin "4") (pinfunction "V-_4") (pintype "bidirectional"))
      (node (ref "IC14") (pin "4") (pinfunction "V-_4") (pintype "bidirectional"))
      (node (ref "JP17") (pin "4") (pinfunction "P$4_4") (pintype "bidirectional"))
    )
    (net (code "105") (name "/V_REF_PRECHAR") (class "Default")
      (node (ref "IC1") (pin "7") (pinfunction "V_REF_PRECHAR_7") (pintype "input"))
      (node (ref "JP7") (pin "2") (pinfunction "2_2") (pintype "passive"))
      (node (ref "TP37") (pin "TP") (pinfunction "TP_TP") (pintype "input"))
    )
    (net (code "106") (name "/V_REF_PRECHAR_BUFF") (class "Default")
      (node (ref "C34") (pin "1") (pinfunction "1_1") (pintype "passive"))
      (node (ref "IC14") (pin "1") (pinfunction "OUTA_1") (pintype "bidirectional"))
      (node (ref "IC14") (pin "2") (pinfunction "-INA_2") (pintype "bidirectional"))
      (node (ref "JP7") (pin "1") (pinfunction "1_1") (pintype "passive"))
    )
    (net (code "107") (name "/~{CS_ADC1}") (class "Default")
      (node (ref "IC22") (pin "P$9") (pinfunction "CNVST_P$9") (pintype "bidirectional"))
      (node (ref "J1") (pin "A44") (pinfunction "A44_A44") (pintype "bidirectional"))
    )
    (net (code "108") (name "/~{CS_ADC2}") (class "Default")
      (node (ref "J1") (pin "A15") (pinfunction "A15_A15") (pintype "bidirectional"))
      (node (ref "U$5") (pin "P$9") (pinfunction "CNVST_P$9") (pintype "bidirectional"))
    )
    (net (code "109") (name "/~{CS_DAC}") (class "Default")
      (node (ref "IC23") (pin "7") (pinfunction "~{SYNC}_7") (pintype "bidirectional"))
      (node (ref "J1") (pin "A17") (pinfunction "A17_A17") (pintype "bidirectional"))
    )
    (net (code "110") (name "Net-(C36-Pad2)") (class "Default")
      (node (ref "C36") (pin "2") (pinfunction "2_2") (pintype "passive"))
      (node (ref "C37") (pin "1") (pinfunction "1_1") (pintype "passive"))
      (node (ref "JP9") (pin "2") (pinfunction "2_2") (pintype "passive"))
    )
    (net (code "111") (name "Net-(C37-Pad2)") (class "Default")
      (node (ref "C37") (pin "2") (pinfunction "2_2") (pintype "passive"))
      (node (ref "JP10") (pin "1") (pinfunction "1_1") (pintype "passive"))
    )
    (net (code "112") (name "Net-(C38-Pad1)") (class "Default")
      (node (ref "C38") (pin "1") (pinfunction "1_1") (pintype "passive"))
      (node (ref "JP1") (pin "2") (pinfunction "2_2") (pintype "passive"))
    )
    (net (code "113") (name "Net-(C42-Pad1)") (class "Default")
      (node (ref "C42") (pin "1") (pinfunction "1_1") (pintype "passive"))
      (node (ref "J1") (pin "B50") (pinfunction "B50_B50") (pintype "bidirectional"))
      (node (ref "R8") (pin "2") (pinfunction "2_2") (pintype "passive"))
    )
    (net (code "114") (name "Net-(IC18-W)") (class "Default")
      (node (ref "IC18") (pin "1") (pinfunction "W_1") (pintype "bidirectional"))
      (node (ref "IC2") (pin "1") (pinfunction "A0_1") (pintype "bidirectional"))
    )
    (net (code "115") (name "Net-(IC19-W)") (class "Default")
      (node (ref "IC19") (pin "1") (pinfunction "W_1") (pintype "bidirectional"))
      (node (ref "IC3") (pin "1") (pinfunction "A0_1") (pintype "bidirectional"))
    )
    (net (code "116") (name "Net-(IC20-W)") (class "Default")
      (node (ref "IC20") (pin "1") (pinfunction "W_1") (pintype "bidirectional"))
      (node (ref "IC4") (pin "1") (pinfunction "A0_1") (pintype "bidirectional"))
    )
    (net (code "117") (name "Net-(J1-PadA46)") (class "Default")
      (node (ref "J1") (pin "A46") (pinfunction "A46_A46") (pintype "bidirectional"))
      (node (ref "J1") (pin "A48") (pinfunction "A48_A48") (pintype "bidirectional"))
    )
    (net (code "118") (name "Net-(J1-PadB1)") (class "Default")
      (node (ref "J1") (pin "B1") (pinfunction "B1_B1") (pintype "bidirectional"))
      (node (ref "R9") (pin "2") (pinfunction "2_2") (pintype "passive"))
    )
    (net (code "119") (name "unconnected-(IC5-N{slash}C-Pad1)") (class "Default")
      (node (ref "IC5") (pin "1") (pinfunction "N/C_1") (pintype "bidirectional"))
    )
    (net (code "120") (name "unconnected-(IC6-N{slash}C-Pad1)") (class "Default")
      (node (ref "IC6") (pin "1") (pinfunction "N/C_1") (pintype "bidirectional"))
    )
    (net (code "121") (name "unconnected-(IC7-N{slash}C-Pad1)") (class "Default")
      (node (ref "IC7") (pin "1") (pinfunction "N/C_1") (pintype "bidirectional"))
    )
    (net (code "122") (name "unconnected-(IC8-N{slash}C-Pad1)") (class "Default")
      (node (ref "IC8") (pin "1") (pinfunction "N/C_1") (pintype "bidirectional"))
    )
    (net (code "123") (name "unconnected-(IC9-GND-Pad4)") (class "Default")
      (node (ref "IC9") (pin "4") (pinfunction "GND_4") (pintype "passive"))
    )
    (net (code "124") (name "unconnected-(IC10-N{slash}C-Pad1)") (class "Default")
      (node (ref "IC10") (pin "1") (pinfunction "N/C_1") (pintype "bidirectional"))
    )
    (net (code "125") (name "unconnected-(IC11-GND-Pad4)") (class "Default")
      (node (ref "IC11") (pin "4") (pinfunction "GND_4") (pintype "passive"))
    )
    (net (code "126") (name "unconnected-(IC13-N{slash}C-Pad1)") (class "Default")
      (node (ref "IC13") (pin "1") (pinfunction "N/C_1") (pintype "bidirectional"))
    )
    (net (code "127") (name "unconnected-(IC14-+INB-Pad5)") (class "Default")
      (node (ref "IC14") (pin "5") (pinfunction "+INB_5") (pintype "bidirectional"))
    )
    (net (code "128") (name "unconnected-(IC14--INB-Pad6)") (class "Default")
      (node (ref "IC14") (pin "6") (pinfunction "-INB_6") (pintype "bidirectional"))
    )
    (net (code "129") (name "unconnected-(IC14-OUTB-Pad7)") (class "Default")
      (node (ref "IC14") (pin "7") (pinfunction "OUTB_7") (pintype "bidirectional"))
    )
    (net (code "130") (name "unconnected-(IC16-N{slash}C-Pad1)") (class "Default")
      (node (ref "IC16") (pin "1") (pinfunction "N/C_1") (pintype "bidirectional"))
    )
    (net (code "131") (name "unconnected-(IC17-N{slash}C-Pad1)") (class "Default")
      (node (ref "IC17") (pin "1") (pinfunction "N/C_1") (pintype "bidirectional"))
    )
    (net (code "132") (name "unconnected-(IC17-VREF-Pad5)") (class "Default")
      (node (ref "IC17") (pin "5") (pinfunction "VREF_5") (pintype "bidirectional"))
    )
    (net (code "133") (name "unconnected-(J1-PadA1)") (class "Default")
      (node (ref "J1") (pin "A1") (pinfunction "A1_A1") (pintype "bidirectional"))
    )
    (net (code "134") (name "unconnected-(J1-PadA2)") (class "Default")
      (node (ref "J1") (pin "A2") (pinfunction "A2_A2") (pintype "bidirectional"))
    )
    (net (code "135") (name "unconnected-(J1-PadA3)") (class "Default")
      (node (ref "J1") (pin "A3") (pinfunction "A3_A3") (pintype "bidirectional"))
    )
    (net (code "136") (name "unconnected-(J1-PadA4)") (class "Default")
      (node (ref "J1") (pin "A4") (pinfunction "A4_A4") (pintype "bidirectional"))
    )
    (net (code "137") (name "unconnected-(J1-PadA5)") (class "Default")
      (node (ref "J1") (pin "A5") (pinfunction "A5_A5") (pintype "bidirectional"))
    )
    (net (code "138") (name "unconnected-(J1-PadA27)") (class "Default")
      (node (ref "J1") (pin "A27") (pinfunction "A27_A27") (pintype "bidirectional"))
    )
    (net (code "139") (name "unconnected-(J1-PadA29)") (class "Default")
      (node (ref "J1") (pin "A29") (pinfunction "A29_A29") (pintype "bidirectional"))
    )
    (net (code "140") (name "unconnected-(J1-PadA31)") (class "Default")
      (node (ref "J1") (pin "A31") (pinfunction "A31_A31") (pintype "bidirectional"))
    )
    (net (code "141") (name "unconnected-(J1-PadA37)") (class "Default")
      (node (ref "J1") (pin "A37") (pinfunction "A37_A37") (pintype "bidirectional"))
    )
    (net (code "142") (name "unconnected-(J1-PadA39)") (class "Default")
      (node (ref "J1") (pin "A39") (pinfunction "A39_A39") (pintype "bidirectional"))
    )
    (net (code "143") (name "unconnected-(J1-PadA41)") (class "Default")
      (node (ref "J1") (pin "A41") (pinfunction "A41_A41") (pintype "bidirectional"))
    )
    (net (code "144") (name "unconnected-(J1-PadA47)") (class "Default")
      (node (ref "J1") (pin "A47") (pinfunction "A47_A47") (pintype "bidirectional"))
    )
    (net (code "145") (name "unconnected-(J1-PadA49)") (class "Default")
      (node (ref "J1") (pin "A49") (pinfunction "A49_A49") (pintype "bidirectional"))
    )
    (net (code "146") (name "unconnected-(J1-PadA50)") (class "Default")
      (node (ref "J1") (pin "A50") (pinfunction "A50_A50") (pintype "bidirectional"))
    )
    (net (code "147") (name "unconnected-(J1-PadB3)") (class "Default")
      (node (ref "J1") (pin "B3") (pinfunction "B3_B3") (pintype "bidirectional"))
    )
    (net (code "148") (name "unconnected-(J1-PadB4)") (class "Default")
      (node (ref "J1") (pin "B4") (pinfunction "B4_B4") (pintype "bidirectional"))
    )
    (net (code "149") (name "unconnected-(J1-PadB46)") (class "Default")
      (node (ref "J1") (pin "B46") (pinfunction "B46_B46") (pintype "bidirectional"))
    )
    (net (code "150") (name "unconnected-(J1-PadB48)") (class "Default")
      (node (ref "J1") (pin "B48") (pinfunction "B48_B48") (pintype "bidirectional"))
    )
    (net (code "151") (name "unconnected-(J1-PadB49)") (class "Default")
      (node (ref "J1") (pin "B49") (pinfunction "B49_B49") (pintype "bidirectional"))
    )
  )
)
